# PCB-CMB-6.net
KiCad netlist of a schematic drawn in EAGLE
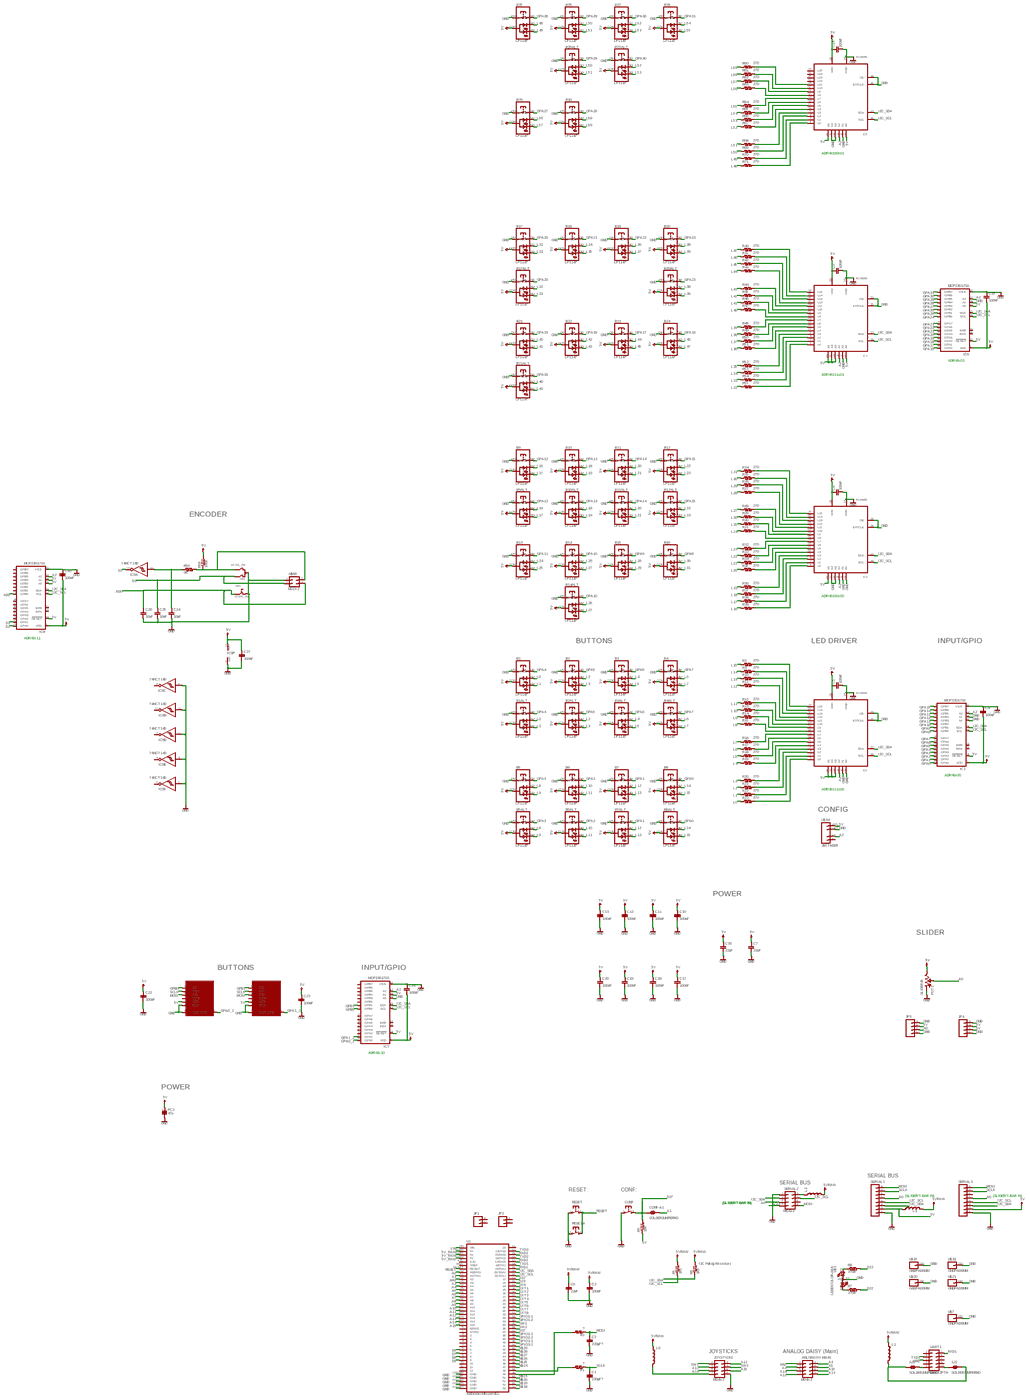
[diagram p0: schematic, sheet 1, overview]
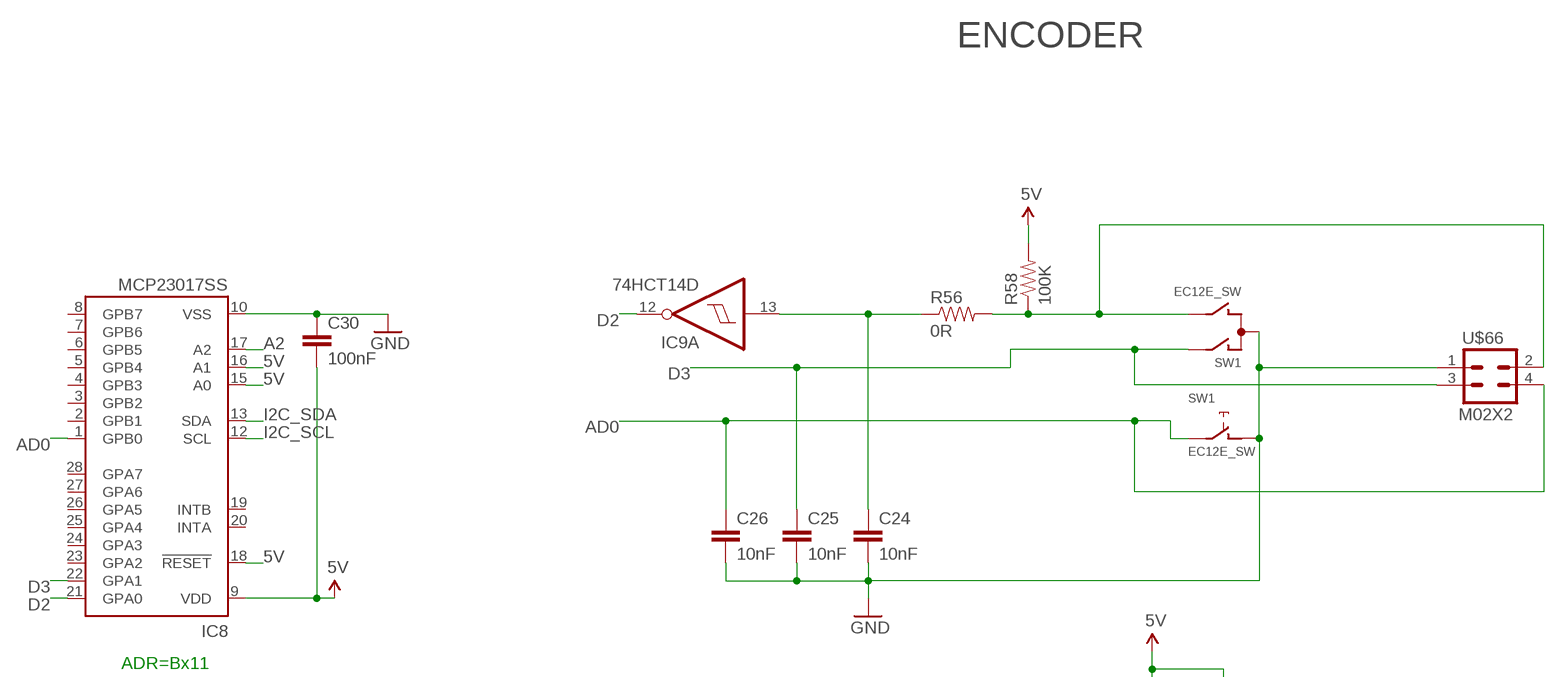
[diagram p1: schematic, sheet 1, part 1 of 6]
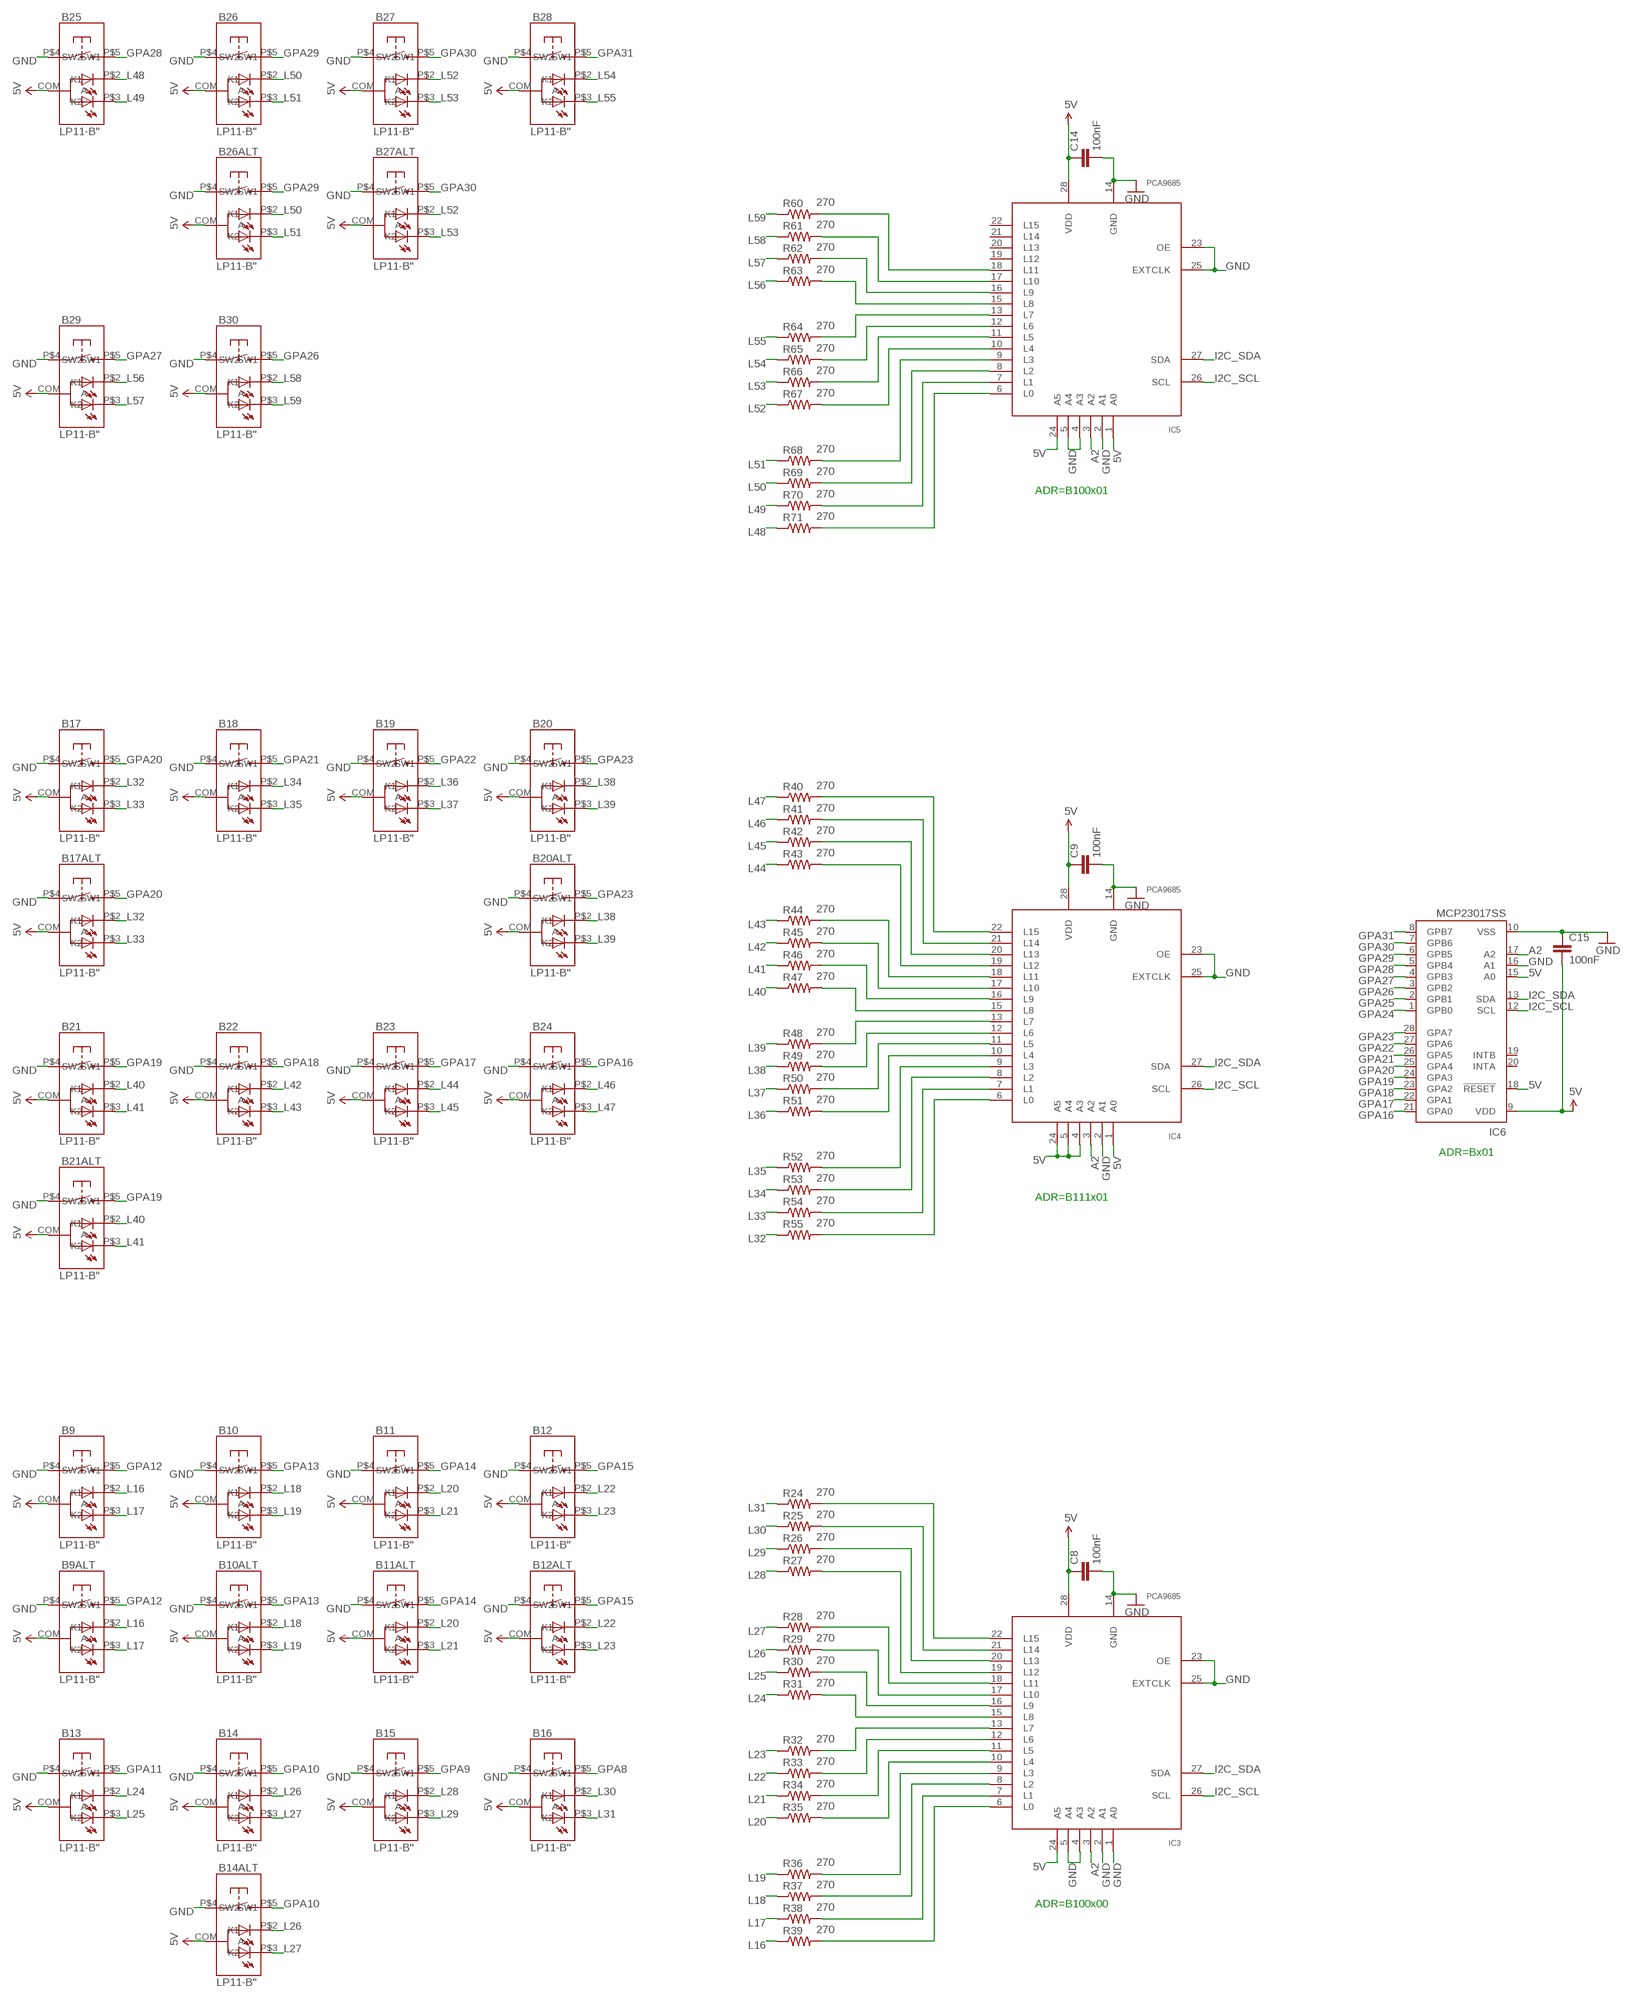
[diagram p2: schematic, sheet 1, part 2 of 6]
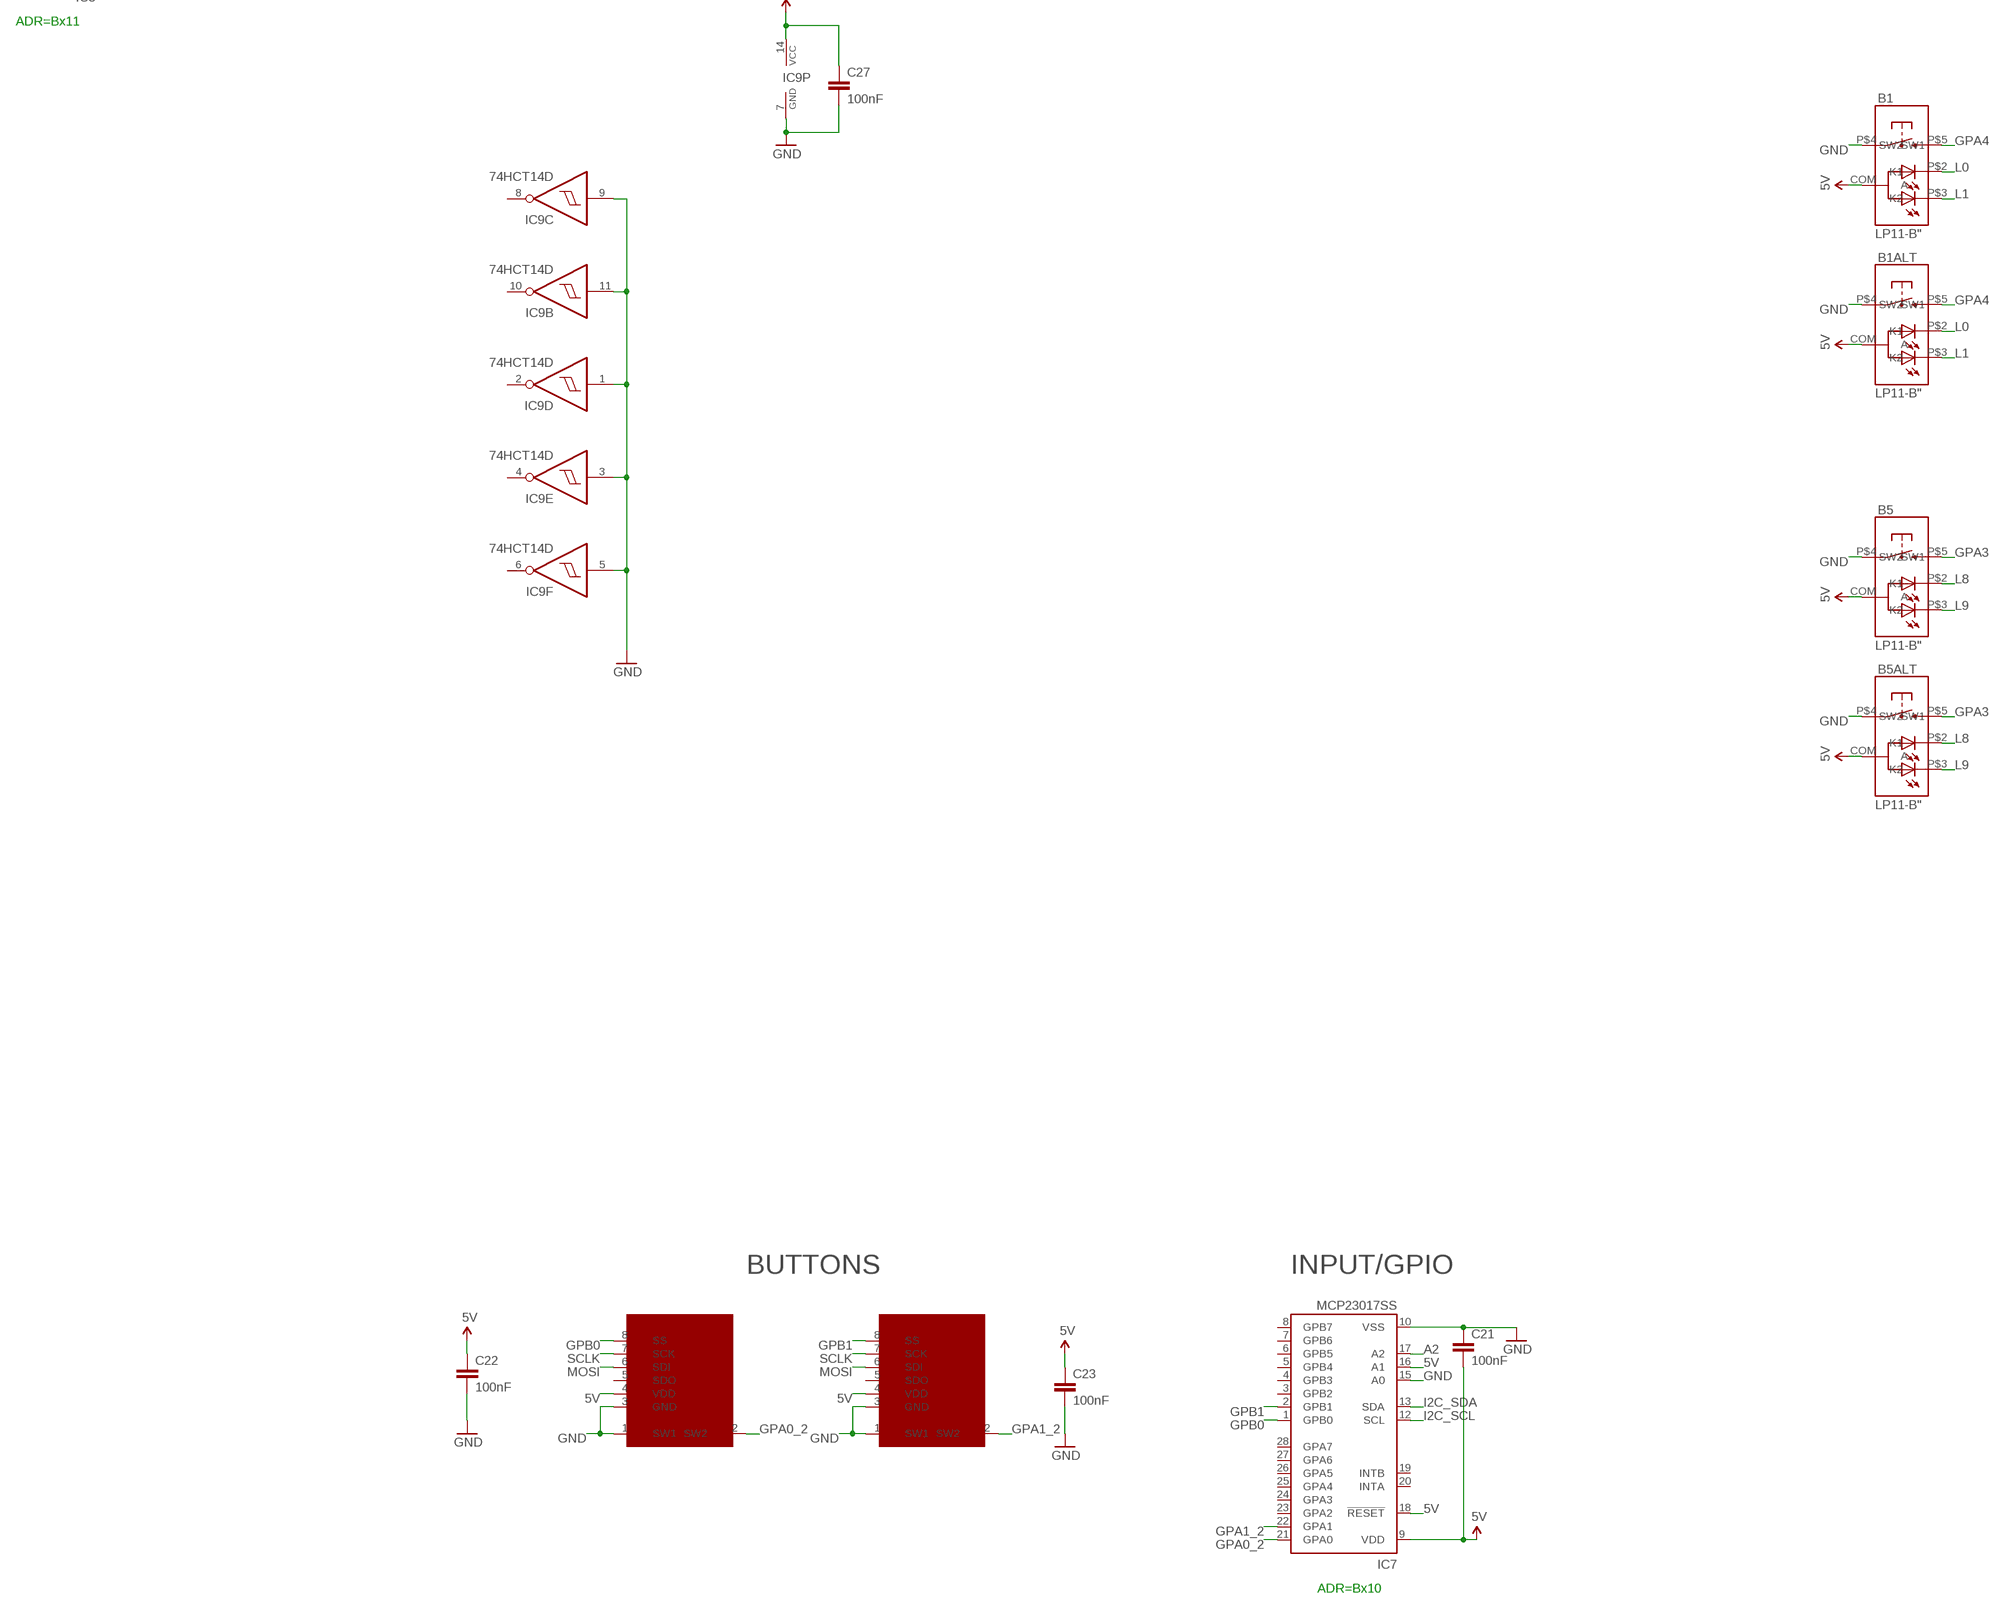
[diagram p3: schematic, sheet 1, part 3 of 6]
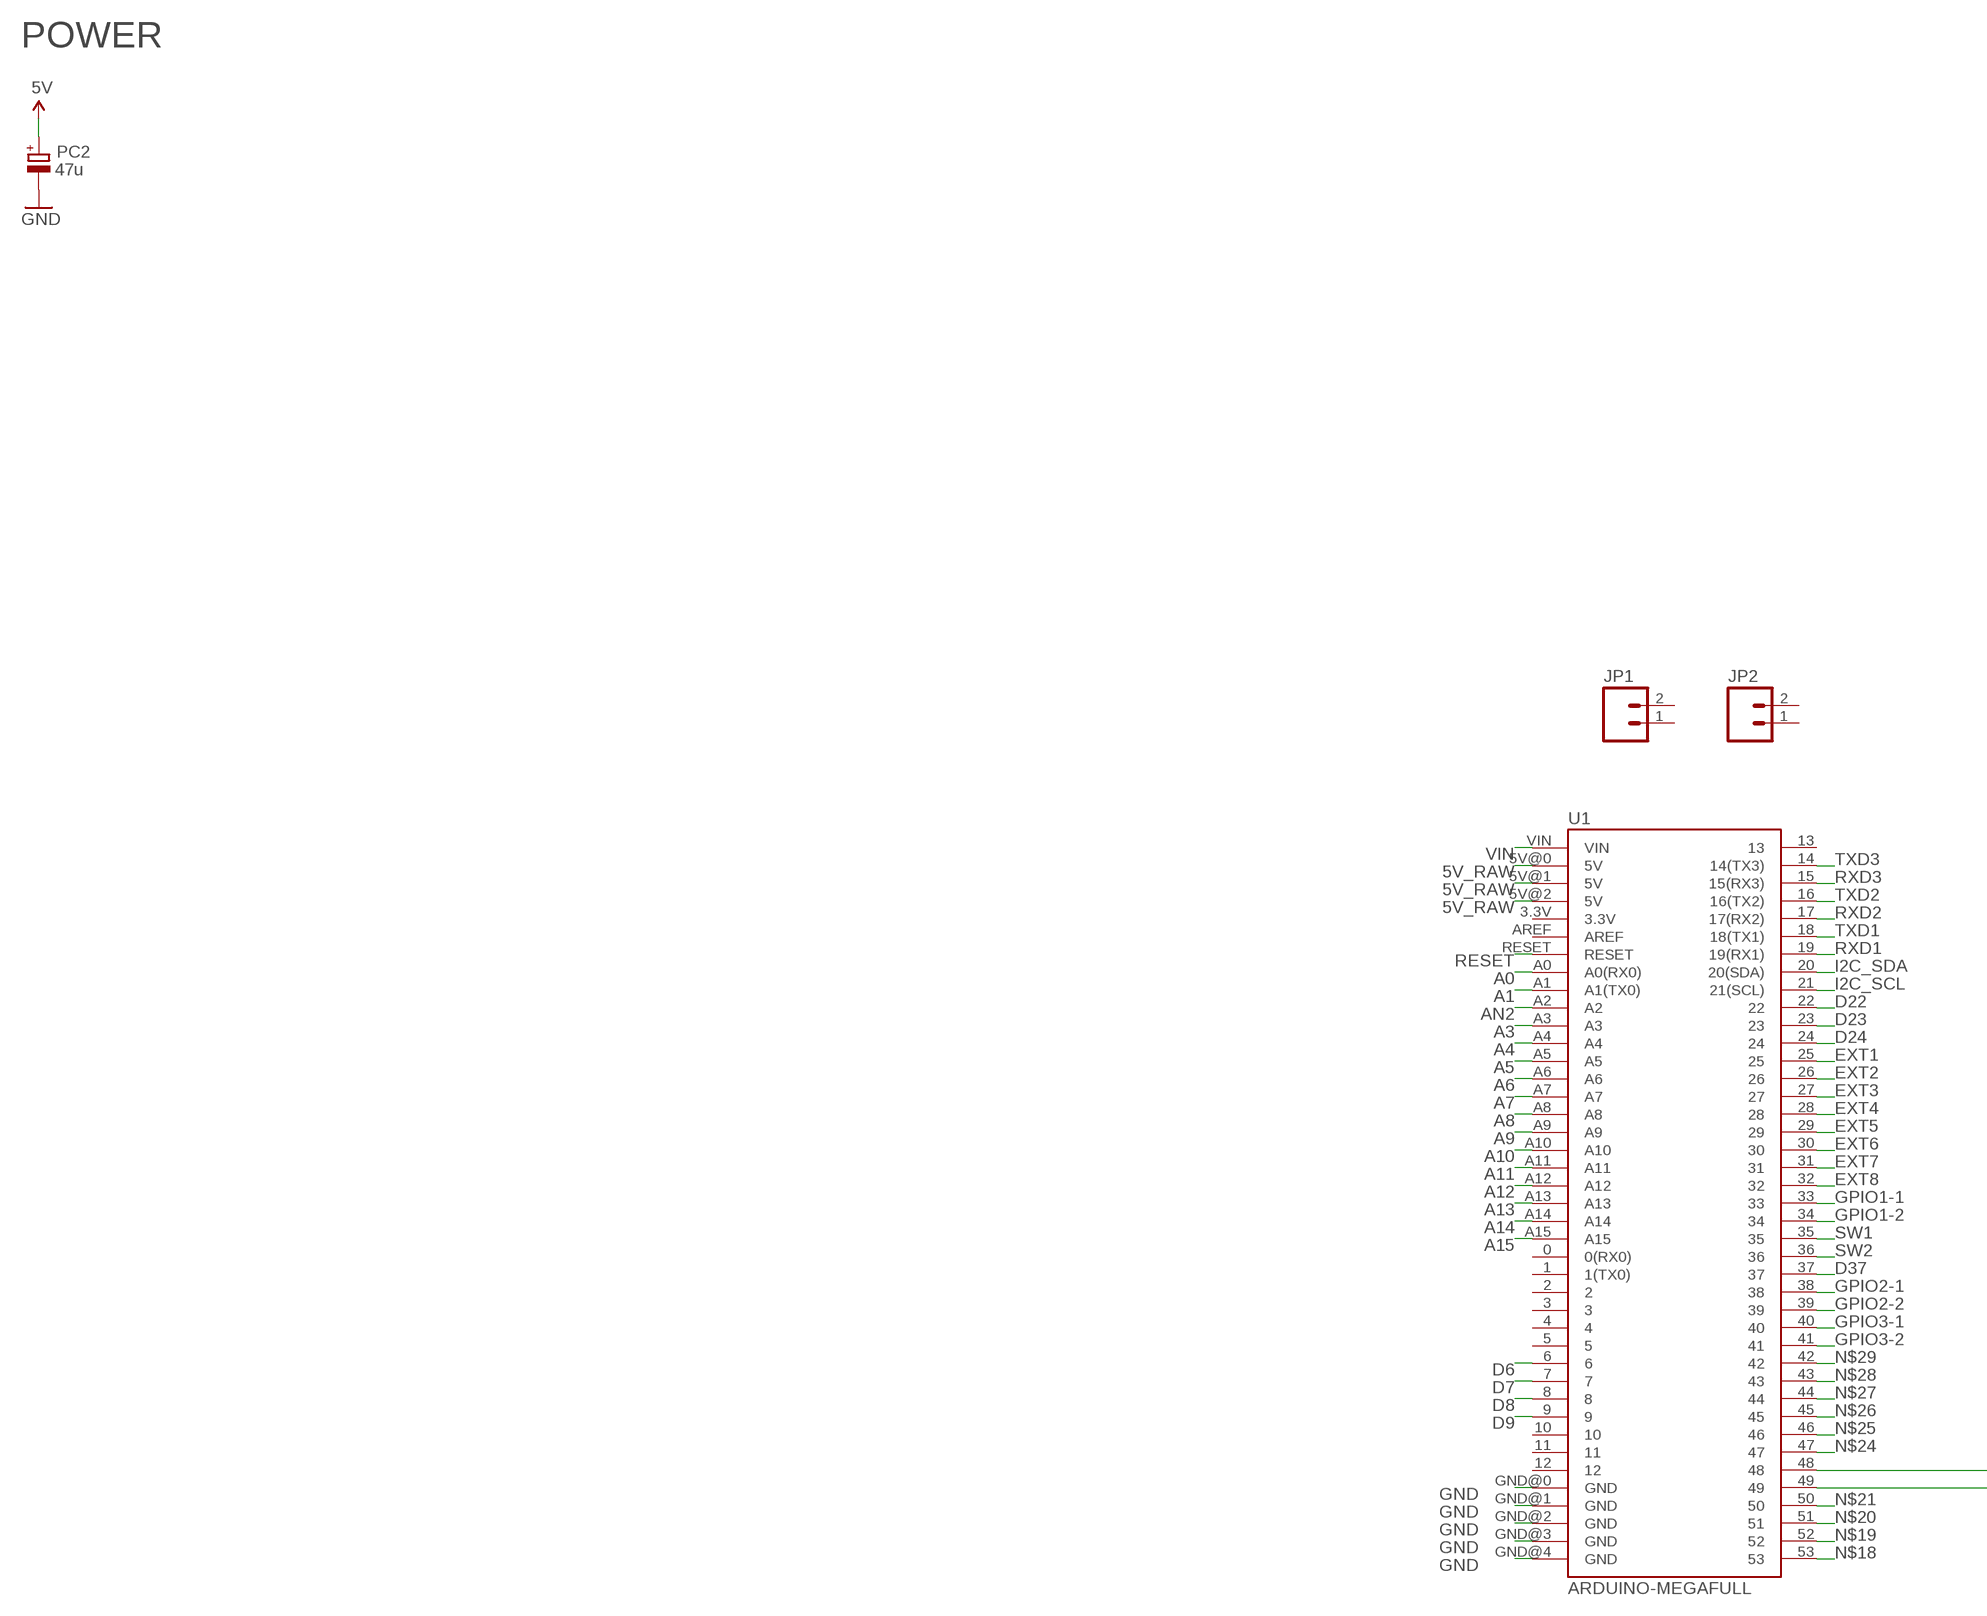
[diagram p4: schematic, sheet 1, part 4 of 6]
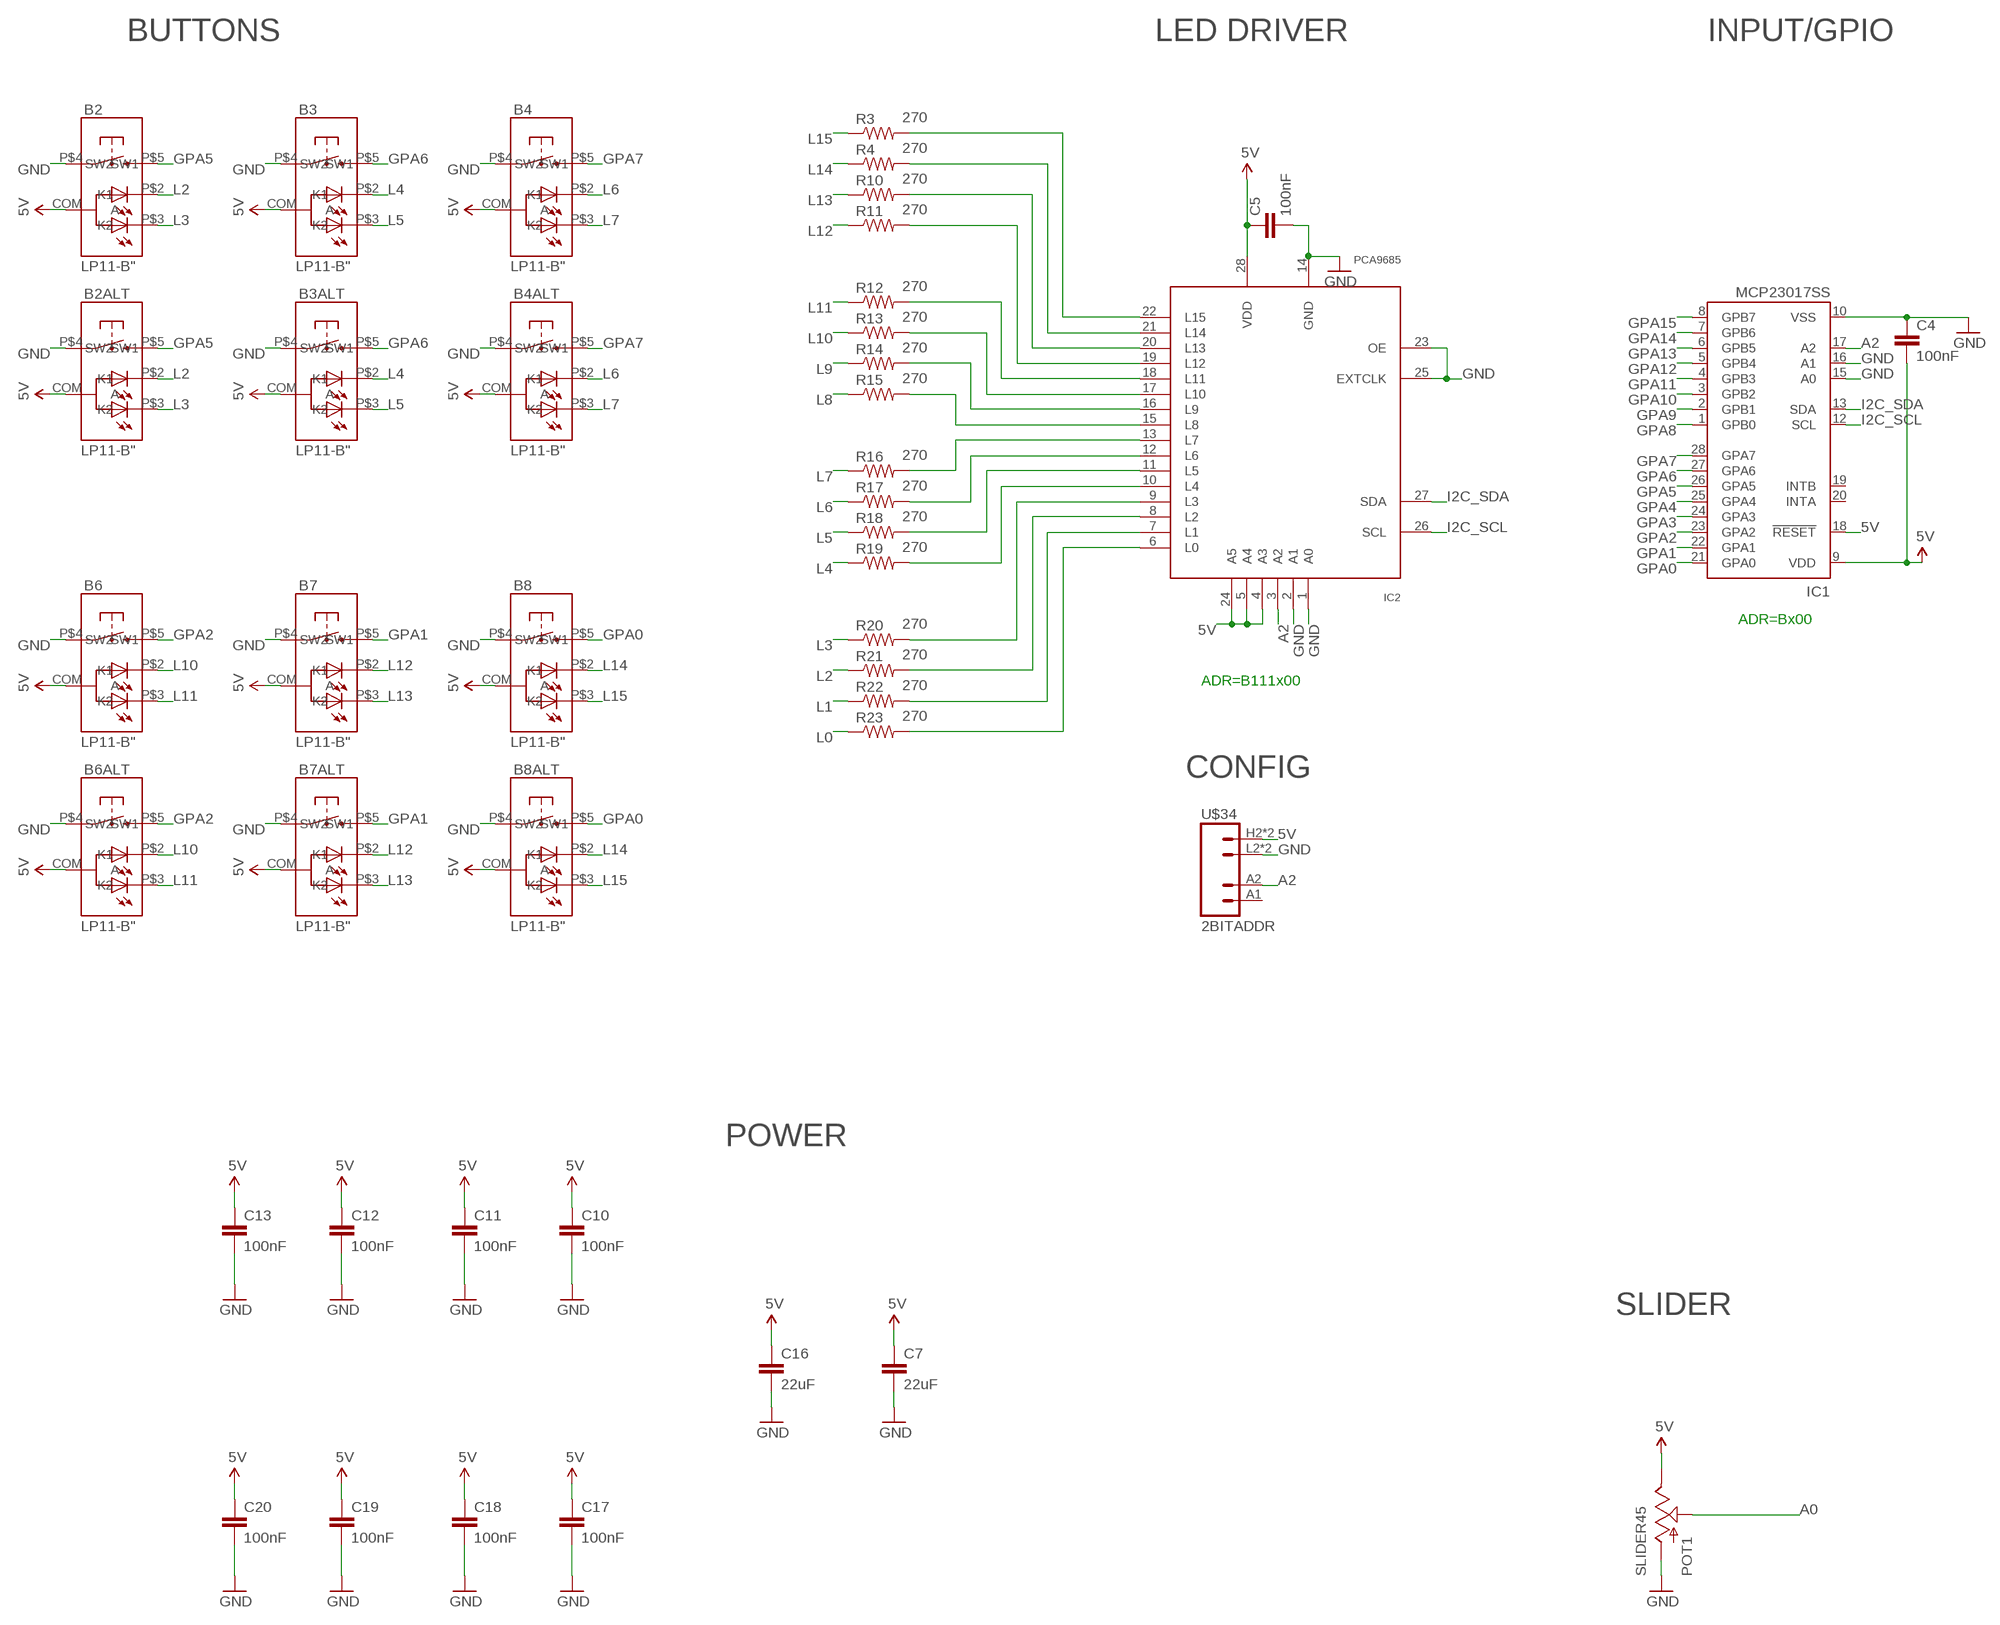
[diagram p5: schematic, sheet 1, part 5 of 6]
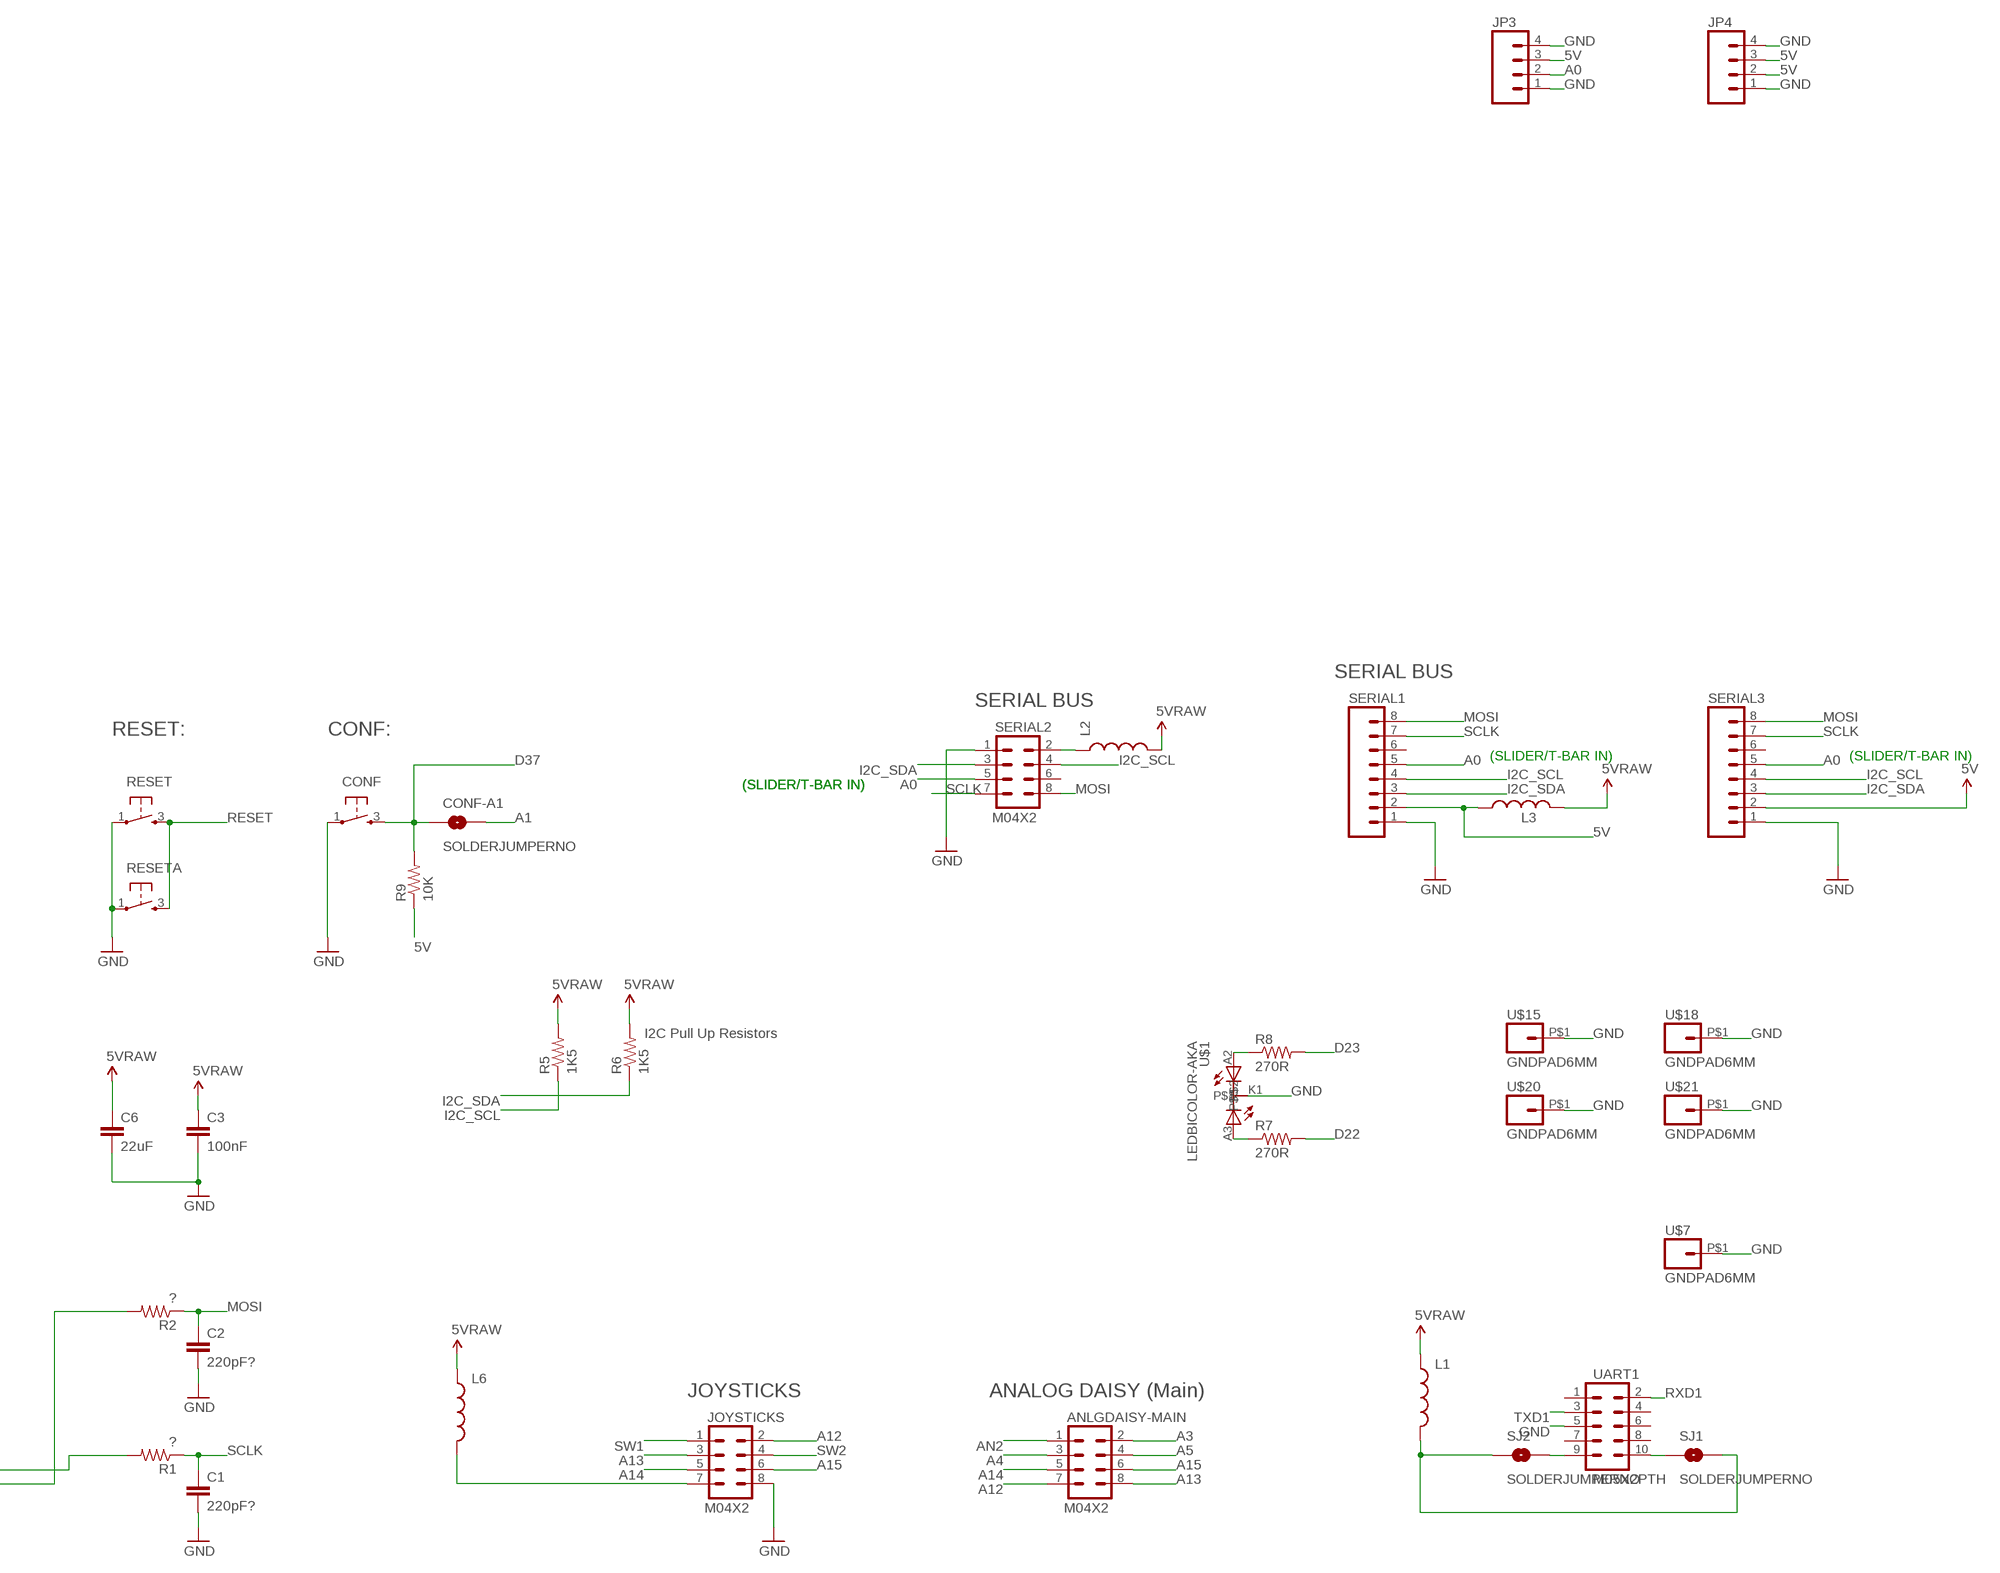
[diagram p6: schematic, sheet 1, part 6 of 6]

(export (version "E")
  (design (tool "Eeschema 10.0.6"))
  (components
    (comp (ref "ANLGDAISY-MAIN")
      (value "M04X2")
      (footprint "eagle-import:2X4")
      (libsource (lib "eagle-import") (part "M04X2"))
    )
    (comp (ref "B1")
      (value "LP11-B\"")
      (footprint "eagle-import:LP11")
      (libsource (lib "eagle-import") (part "LP11-B{dblquote}"))
    )
    (comp (ref "B1ALT")
      (value "LP11-B\"")
      (footprint "eagle-import:LP11")
      (libsource (lib "eagle-import") (part "LP11-B{dblquote}"))
    )
    (comp (ref "B2")
      (value "LP11-B\"")
      (footprint "eagle-import:LP11")
      (libsource (lib "eagle-import") (part "LP11-B{dblquote}"))
    )
    (comp (ref "B2ALT")
      (value "LP11-B\"")
      (footprint "eagle-import:LP11")
      (libsource (lib "eagle-import") (part "LP11-B{dblquote}"))
    )
    (comp (ref "B3")
      (value "LP11-B\"")
      (footprint "eagle-import:LP11")
      (libsource (lib "eagle-import") (part "LP11-B{dblquote}"))
    )
    (comp (ref "B3ALT")
      (value "LP11-B\"")
      (footprint "eagle-import:LP11")
      (libsource (lib "eagle-import") (part "LP11-B{dblquote}"))
    )
    (comp (ref "B4")
      (value "LP11-B\"")
      (footprint "eagle-import:LP11")
      (libsource (lib "eagle-import") (part "LP11-B{dblquote}"))
    )
    (comp (ref "B4ALT")
      (value "LP11-B\"")
      (footprint "eagle-import:LP11")
      (libsource (lib "eagle-import") (part "LP11-B{dblquote}"))
    )
    (comp (ref "B5")
      (value "LP11-B\"")
      (footprint "eagle-import:LP11")
      (libsource (lib "eagle-import") (part "LP11-B{dblquote}"))
    )
    (comp (ref "B5ALT")
      (value "LP11-B\"")
      (footprint "eagle-import:LP11")
      (libsource (lib "eagle-import") (part "LP11-B{dblquote}"))
    )
    (comp (ref "B6")
      (value "LP11-B\"")
      (footprint "eagle-import:LP11")
      (libsource (lib "eagle-import") (part "LP11-B{dblquote}"))
    )
    (comp (ref "B6ALT")
      (value "LP11-B\"")
      (footprint "eagle-import:LP11")
      (libsource (lib "eagle-import") (part "LP11-B{dblquote}"))
    )
    (comp (ref "B7")
      (value "LP11-B\"")
      (footprint "eagle-import:LP11")
      (libsource (lib "eagle-import") (part "LP11-B{dblquote}"))
    )
    (comp (ref "B7ALT")
      (value "LP11-B\"")
      (footprint "eagle-import:LP11")
      (libsource (lib "eagle-import") (part "LP11-B{dblquote}"))
    )
    (comp (ref "B8")
      (value "LP11-B\"")
      (footprint "eagle-import:LP11")
      (libsource (lib "eagle-import") (part "LP11-B{dblquote}"))
    )
    (comp (ref "B8ALT")
      (value "LP11-B\"")
      (footprint "eagle-import:LP11")
      (libsource (lib "eagle-import") (part "LP11-B{dblquote}"))
    )
    (comp (ref "B9")
      (value "LP11-B\"")
      (footprint "eagle-import:LP11")
      (libsource (lib "eagle-import") (part "LP11-B{dblquote}"))
    )
    (comp (ref "B9ALT")
      (value "LP11-B\"")
      (footprint "eagle-import:LP11")
      (libsource (lib "eagle-import") (part "LP11-B{dblquote}"))
    )
    (comp (ref "B10")
      (value "LP11-B\"")
      (footprint "eagle-import:LP11")
      (libsource (lib "eagle-import") (part "LP11-B{dblquote}"))
    )
    (comp (ref "B10ALT")
      (value "LP11-B\"")
      (footprint "eagle-import:LP11")
      (libsource (lib "eagle-import") (part "LP11-B{dblquote}"))
    )
    (comp (ref "B11")
      (value "LP11-B\"")
      (footprint "eagle-import:LP11")
      (libsource (lib "eagle-import") (part "LP11-B{dblquote}"))
    )
    (comp (ref "B11ALT")
      (value "LP11-B\"")
      (footprint "eagle-import:LP11")
      (libsource (lib "eagle-import") (part "LP11-B{dblquote}"))
    )
    (comp (ref "B12")
      (value "LP11-B\"")
      (footprint "eagle-import:LP11")
      (libsource (lib "eagle-import") (part "LP11-B{dblquote}"))
    )
    (comp (ref "B12ALT")
      (value "LP11-B\"")
      (footprint "eagle-import:LP11")
      (libsource (lib "eagle-import") (part "LP11-B{dblquote}"))
    )
    (comp (ref "B13")
      (value "LP11-B\"")
      (footprint "eagle-import:LP11")
      (libsource (lib "eagle-import") (part "LP11-B{dblquote}"))
    )
    (comp (ref "B14")
      (value "LP11-B\"")
      (footprint "eagle-import:LP11")
      (libsource (lib "eagle-import") (part "LP11-B{dblquote}"))
    )
    (comp (ref "B14ALT")
      (value "LP11-B\"")
      (footprint "eagle-import:LP11")
      (libsource (lib "eagle-import") (part "LP11-B{dblquote}"))
    )
    (comp (ref "B15")
      (value "LP11-B\"")
      (footprint "eagle-import:LP11")
      (libsource (lib "eagle-import") (part "LP11-B{dblquote}"))
    )
    (comp (ref "B16")
      (value "LP11-B\"")
      (footprint "eagle-import:LP11")
      (libsource (lib "eagle-import") (part "LP11-B{dblquote}"))
    )
    (comp (ref "B17")
      (value "LP11-B\"")
      (footprint "eagle-import:LP11")
      (libsource (lib "eagle-import") (part "LP11-B{dblquote}"))
    )
    (comp (ref "B17ALT")
      (value "LP11-B\"")
      (footprint "eagle-import:LP11")
      (libsource (lib "eagle-import") (part "LP11-B{dblquote}"))
    )
    (comp (ref "B18")
      (value "LP11-B\"")
      (footprint "eagle-import:LP11")
      (libsource (lib "eagle-import") (part "LP11-B{dblquote}"))
    )
    (comp (ref "B19")
      (value "LP11-B\"")
      (footprint "eagle-import:LP11")
      (libsource (lib "eagle-import") (part "LP11-B{dblquote}"))
    )
    (comp (ref "B20")
      (value "LP11-B\"")
      (footprint "eagle-import:LP11")
      (libsource (lib "eagle-import") (part "LP11-B{dblquote}"))
    )
    (comp (ref "B20ALT")
      (value "LP11-B\"")
      (footprint "eagle-import:LP11")
      (libsource (lib "eagle-import") (part "LP11-B{dblquote}"))
    )
    (comp (ref "B21")
      (value "LP11-B\"")
      (footprint "eagle-import:LP11")
      (libsource (lib "eagle-import") (part "LP11-B{dblquote}"))
    )
    (comp (ref "B21ALT")
      (value "LP11-B\"")
      (footprint "eagle-import:LP11")
      (libsource (lib "eagle-import") (part "LP11-B{dblquote}"))
    )
    (comp (ref "B22")
      (value "LP11-B\"")
      (footprint "eagle-import:LP11")
      (libsource (lib "eagle-import") (part "LP11-B{dblquote}"))
    )
    (comp (ref "B23")
      (value "LP11-B\"")
      (footprint "eagle-import:LP11")
      (libsource (lib "eagle-import") (part "LP11-B{dblquote}"))
    )
    (comp (ref "B24")
      (value "LP11-B\"")
      (footprint "eagle-import:LP11")
      (libsource (lib "eagle-import") (part "LP11-B{dblquote}"))
    )
    (comp (ref "B25")
      (value "LP11-B\"")
      (footprint "eagle-import:LP11")
      (libsource (lib "eagle-import") (part "LP11-B{dblquote}"))
    )
    (comp (ref "B26")
      (value "LP11-B\"")
      (footprint "eagle-import:LP11")
      (libsource (lib "eagle-import") (part "LP11-B{dblquote}"))
    )
    (comp (ref "B26ALT")
      (value "LP11-B\"")
      (footprint "eagle-import:LP11")
      (libsource (lib "eagle-import") (part "LP11-B{dblquote}"))
    )
    (comp (ref "B27")
      (value "LP11-B\"")
      (footprint "eagle-import:LP11")
      (libsource (lib "eagle-import") (part "LP11-B{dblquote}"))
    )
    (comp (ref "B27ALT")
      (value "LP11-B\"")
      (footprint "eagle-import:LP11")
      (libsource (lib "eagle-import") (part "LP11-B{dblquote}"))
    )
    (comp (ref "B28")
      (value "LP11-B\"")
      (footprint "eagle-import:LP11")
      (libsource (lib "eagle-import") (part "LP11-B{dblquote}"))
    )
    (comp (ref "B29")
      (value "LP11-B\"")
      (footprint "eagle-import:LP11")
      (libsource (lib "eagle-import") (part "LP11-B{dblquote}"))
    )
    (comp (ref "B30")
      (value "LP11-B\"")
      (footprint "eagle-import:LP11")
      (libsource (lib "eagle-import") (part "LP11-B{dblquote}"))
    )
    (comp (ref "C1")
      (value "220pF?")
      (footprint "eagle-import:0603-CAP")
      (libsource (lib "eagle-import") (part "CAP0603-CAP"))
    )
    (comp (ref "C2")
      (value "220pF?")
      (footprint "eagle-import:0603-CAP")
      (libsource (lib "eagle-import") (part "CAP0603-CAP"))
    )
    (comp (ref "C3")
      (value "100nF")
      (footprint "eagle-import:0603-CAP")
      (libsource (lib "eagle-import") (part "CAP0603-CAP"))
    )
    (comp (ref "C4")
      (value "100nF")
      (footprint "eagle-import:0603-CAP")
      (libsource (lib "eagle-import") (part "CAP0603-CAP"))
    )
    (comp (ref "C5")
      (value "100nF")
      (footprint "eagle-import:0603-CAP")
      (libsource (lib "eagle-import") (part "CAP0603-CAP"))
    )
    (comp (ref "C6")
      (value "22uF")
      (footprint "eagle-import:0805")
      (libsource (lib "eagle-import") (part "CAP0805"))
    )
    (comp (ref "C7")
      (value "22uF")
      (footprint "eagle-import:0805")
      (libsource (lib "eagle-import") (part "CAP0805"))
    )
    (comp (ref "C8")
      (value "100nF")
      (footprint "eagle-import:0603-CAP")
      (libsource (lib "eagle-import") (part "CAP0603-CAP"))
    )
    (comp (ref "C9")
      (value "100nF")
      (footprint "eagle-import:0603-CAP")
      (libsource (lib "eagle-import") (part "CAP0603-CAP"))
    )
    (comp (ref "C10")
      (value "100nF")
      (footprint "eagle-import:0603-CAP")
      (libsource (lib "eagle-import") (part "CAP0603-CAP"))
    )
    (comp (ref "C11")
      (value "100nF")
      (footprint "eagle-import:0603-CAP")
      (libsource (lib "eagle-import") (part "CAP0603-CAP"))
    )
    (comp (ref "C12")
      (value "100nF")
      (footprint "eagle-import:0603-CAP")
      (libsource (lib "eagle-import") (part "CAP0603-CAP"))
    )
    (comp (ref "C13")
      (value "100nF")
      (footprint "eagle-import:0603-CAP")
      (libsource (lib "eagle-import") (part "CAP0603-CAP"))
    )
    (comp (ref "C14")
      (value "100nF")
      (footprint "eagle-import:0603-CAP")
      (libsource (lib "eagle-import") (part "CAP0603-CAP"))
    )
    (comp (ref "C15")
      (value "100nF")
      (footprint "eagle-import:0603-CAP")
      (libsource (lib "eagle-import") (part "CAP0603-CAP"))
    )
    (comp (ref "C16")
      (value "22uF")
      (footprint "eagle-import:0805")
      (libsource (lib "eagle-import") (part "CAP0805"))
    )
    (comp (ref "C17")
      (value "100nF")
      (footprint "eagle-import:0603-CAP")
      (libsource (lib "eagle-import") (part "CAP0603-CAP"))
    )
    (comp (ref "C18")
      (value "100nF")
      (footprint "eagle-import:0603-CAP")
      (libsource (lib "eagle-import") (part "CAP0603-CAP"))
    )
    (comp (ref "C19")
      (value "100nF")
      (footprint "eagle-import:0603-CAP")
      (libsource (lib "eagle-import") (part "CAP0603-CAP"))
    )
    (comp (ref "C20")
      (value "100nF")
      (footprint "eagle-import:0603-CAP")
      (libsource (lib "eagle-import") (part "CAP0603-CAP"))
    )
    (comp (ref "C21")
      (value "100nF")
      (footprint "eagle-import:0603-CAP")
      (libsource (lib "eagle-import") (part "CAP0603-CAP"))
    )
    (comp (ref "C22")
      (value "100nF")
      (footprint "eagle-import:0603-CAP")
      (libsource (lib "eagle-import") (part "CAP0603-CAP"))
    )
    (comp (ref "C23")
      (value "100nF")
      (footprint "eagle-import:0603-CAP")
      (libsource (lib "eagle-import") (part "CAP0603-CAP"))
    )
    (comp (ref "C24")
      (value "10nF")
      (footprint "eagle-import:0603-CAP")
      (libsource (lib "eagle-import") (part "CAP0603-CAP"))
    )
    (comp (ref "C25")
      (value "10nF")
      (footprint "eagle-import:0603-CAP")
      (libsource (lib "eagle-import") (part "CAP0603-CAP"))
    )
    (comp (ref "C26")
      (value "10nF")
      (footprint "eagle-import:0603-CAP")
      (libsource (lib "eagle-import") (part "CAP0603-CAP"))
    )
    (comp (ref "C27")
      (value "100nF")
      (footprint "eagle-import:0603-CAP")
      (libsource (lib "eagle-import") (part "CAP0603-CAP"))
    )
    (comp (ref "C30")
      (value "100nF")
      (footprint "eagle-import:0603-CAP")
      (libsource (lib "eagle-import") (part "CAP0603-CAP"))
    )
    (comp (ref "CONF")
      (value "TAC_SWITCH")
      (footprint "eagle-import:PUSHBUTTON")
      (libsource (lib "eagle-import") (part "TAC_SWITCH"))
    )
    (comp (ref "CONF-A1")
      (value "SOLDERJUMPERNO")
      (footprint "eagle-import:SJ_2S-NO")
      (libsource (lib "eagle-import") (part "SOLDERJUMPERNO"))
    )
    (comp (ref "IC1")
      (value "MCP23017SS")
      (footprint "eagle-import:SSOP28")
      (fields
        (field (name "MF") "MICROCHIP")
        (field (name "MPN") "MCP23017-E/SS")
        (field (name "MPN_1") "MCP23017-E/SS")
        (field (name "OC_FARNELL") "1467674")
        (field (name "OC_NEWARK") "31K2960")
      )
      (libsource (lib "eagle-import") (part "MCP23017SS"))
    )
    (comp (ref "IC2")
      (value "PCA9685")
      (footprint "eagle-import:TSSOP28")
      (libsource (lib "eagle-import") (part "PCA9685"))
    )
    (comp (ref "IC3")
      (value "PCA9685")
      (footprint "eagle-import:TSSOP28")
      (libsource (lib "eagle-import") (part "PCA9685"))
    )
    (comp (ref "IC4")
      (value "PCA9685")
      (footprint "eagle-import:TSSOP28")
      (libsource (lib "eagle-import") (part "PCA9685"))
    )
    (comp (ref "IC5")
      (value "PCA9685")
      (footprint "eagle-import:TSSOP28")
      (libsource (lib "eagle-import") (part "PCA9685"))
    )
    (comp (ref "IC6")
      (value "MCP23017SS")
      (footprint "eagle-import:SSOP28")
      (fields
        (field (name "MF") "MICROCHIP")
        (field (name "MPN") "MCP23017-E/SS")
        (field (name "MPN_1") "MCP23017-E/SS")
        (field (name "OC_FARNELL") "1467674")
        (field (name "OC_NEWARK") "31K2960")
      )
      (libsource (lib "eagle-import") (part "MCP23017SS"))
    )
    (comp (ref "IC7")
      (value "MCP23017SS")
      (footprint "eagle-import:SSOP28")
      (fields
        (field (name "MF") "MICROCHIP")
        (field (name "MPN") "MCP23017-E/SS")
        (field (name "MPN_1") "MCP23017-E/SS")
        (field (name "OC_FARNELL") "1467674")
        (field (name "OC_NEWARK") "31K2960")
      )
      (libsource (lib "eagle-import") (part "MCP23017SS"))
    )
    (comp (ref "IC8")
      (value "MCP23017SS")
      (footprint "eagle-import:SSOP28")
      (fields
        (field (name "MF") "MICROCHIP")
        (field (name "MPN") "MCP23017-E/SS")
        (field (name "MPN_1") "MCP23017-E/SS")
        (field (name "OC_FARNELL") "1467674")
        (field (name "OC_NEWARK") "31K2960")
      )
      (libsource (lib "eagle-import") (part "MCP23017SS"))
    )
    (comp (ref "IC9")
      (value "74HCT14D")
      (footprint "eagle-import:SO14")
      (libsource (lib "eagle-import") (part "7414DHCT"))
    )
    (comp (ref "JOYSTICKS")
      (value "M04X2")
      (footprint "eagle-import:2X4")
      (libsource (lib "eagle-import") (part "M04X2"))
    )
    (comp (ref "JP1")
      (value "M02PTH")
      (footprint "eagle-import:1X02")
      (libsource (lib "eagle-import") (part "M02PTH"))
    )
    (comp (ref "JP2")
      (value "M02PTH")
      (footprint "eagle-import:1X02")
      (libsource (lib "eagle-import") (part "M02PTH"))
    )
    (comp (ref "JP3")
      (value "M04PTH")
      (footprint "eagle-import:1X04")
      (libsource (lib "eagle-import") (part "M04PTH"))
    )
    (comp (ref "JP4")
      (value "M04PTH")
      (footprint "eagle-import:1X04")
      (libsource (lib "eagle-import") (part "M04PTH"))
    )
    (comp (ref "L1")
      (value "INDUCTOR0805")
      (footprint "eagle-import:0805")
      (libsource (lib "eagle-import") (part "INDUCTOR0805"))
    )
    (comp (ref "L2")
      (value "INDUCTOR0805")
      (footprint "eagle-import:0805")
      (libsource (lib "eagle-import") (part "INDUCTOR0805"))
    )
    (comp (ref "L3")
      (value "INDUCTOR0805")
      (footprint "eagle-import:0805")
      (libsource (lib "eagle-import") (part "INDUCTOR0805"))
    )
    (comp (ref "L6")
      (value "INDUCTOR0805")
      (footprint "eagle-import:0805")
      (libsource (lib "eagle-import") (part "INDUCTOR0805"))
    )
    (comp (ref "PC2")
      (value "47u")
      (footprint "eagle-import:PANASONIC_D")
      (libsource (lib "eagle-import") (part "CPOL-EUD"))
    )
    (comp (ref "POT1")
      (value "SLIDER45")
      (footprint "eagle-import:SLIDER45")
      (libsource (lib "eagle-import") (part "SLIDER45"))
    )
    (comp (ref "R1")
      (value "?")
      (footprint "eagle-import:0603-RES")
      (libsource (lib "eagle-import") (part "RESISTOR0603-RES"))
    )
    (comp (ref "R2")
      (value "?")
      (footprint "eagle-import:0603-RES")
      (libsource (lib "eagle-import") (part "RESISTOR0603-RES"))
    )
    (comp (ref "R3")
      (value "270")
      (footprint "eagle-import:0603-RES")
      (libsource (lib "eagle-import") (part "RESISTOR0603-RES"))
    )
    (comp (ref "R4")
      (value "270")
      (footprint "eagle-import:0603-RES")
      (libsource (lib "eagle-import") (part "RESISTOR0603-RES"))
    )
    (comp (ref "R5")
      (value "1K5")
      (footprint "eagle-import:0603-RES")
      (libsource (lib "eagle-import") (part "RESISTOR0603-RES"))
    )
    (comp (ref "R6")
      (value "1K5")
      (footprint "eagle-import:0603-RES")
      (libsource (lib "eagle-import") (part "RESISTOR0603-RES"))
    )
    (comp (ref "R7")
      (value "270R")
      (footprint "eagle-import:0603-RES")
      (libsource (lib "eagle-import") (part "RESISTOR0603-RES"))
    )
    (comp (ref "R8")
      (value "270R")
      (footprint "eagle-import:0603-RES")
      (libsource (lib "eagle-import") (part "RESISTOR0603-RES"))
    )
    (comp (ref "R9")
      (value "10K")
      (footprint "eagle-import:0603-RES")
      (libsource (lib "eagle-import") (part "RESISTOR0603-RES"))
    )
    (comp (ref "R10")
      (value "270")
      (footprint "eagle-import:0603-RES")
      (libsource (lib "eagle-import") (part "RESISTOR0603-RES"))
    )
    (comp (ref "R11")
      (value "270")
      (footprint "eagle-import:0603-RES")
      (libsource (lib "eagle-import") (part "RESISTOR0603-RES"))
    )
    (comp (ref "R12")
      (value "270")
      (footprint "eagle-import:0603-RES")
      (libsource (lib "eagle-import") (part "RESISTOR0603-RES"))
    )
    (comp (ref "R13")
      (value "270")
      (footprint "eagle-import:0603-RES")
      (libsource (lib "eagle-import") (part "RESISTOR0603-RES"))
    )
    (comp (ref "R14")
      (value "270")
      (footprint "eagle-import:0603-RES")
      (libsource (lib "eagle-import") (part "RESISTOR0603-RES"))
    )
    (comp (ref "R15")
      (value "270")
      (footprint "eagle-import:0603-RES")
      (libsource (lib "eagle-import") (part "RESISTOR0603-RES"))
    )
    (comp (ref "R16")
      (value "270")
      (footprint "eagle-import:0603-RES")
      (libsource (lib "eagle-import") (part "RESISTOR0603-RES"))
    )
    (comp (ref "R17")
      (value "270")
      (footprint "eagle-import:0603-RES")
      (libsource (lib "eagle-import") (part "RESISTOR0603-RES"))
    )
    (comp (ref "R18")
      (value "270")
      (footprint "eagle-import:0603-RES")
      (libsource (lib "eagle-import") (part "RESISTOR0603-RES"))
    )
    (comp (ref "R19")
      (value "270")
      (footprint "eagle-import:0603-RES")
      (libsource (lib "eagle-import") (part "RESISTOR0603-RES"))
    )
    (comp (ref "R20")
      (value "270")
      (footprint "eagle-import:0603-RES")
      (libsource (lib "eagle-import") (part "RESISTOR0603-RES"))
    )
    (comp (ref "R21")
      (value "270")
      (footprint "eagle-import:0603-RES")
      (libsource (lib "eagle-import") (part "RESISTOR0603-RES"))
    )
    (comp (ref "R22")
      (value "270")
      (footprint "eagle-import:0603-RES")
      (libsource (lib "eagle-import") (part "RESISTOR0603-RES"))
    )
    (comp (ref "R23")
      (value "270")
      (footprint "eagle-import:0603-RES")
      (libsource (lib "eagle-import") (part "RESISTOR0603-RES"))
    )
    (comp (ref "R24")
      (value "270")
      (footprint "eagle-import:0603-RES")
      (libsource (lib "eagle-import") (part "RESISTOR0603-RES"))
    )
    (comp (ref "R25")
      (value "270")
      (footprint "eagle-import:0603-RES")
      (libsource (lib "eagle-import") (part "RESISTOR0603-RES"))
    )
    (comp (ref "R26")
      (value "270")
      (footprint "eagle-import:0603-RES")
      (libsource (lib "eagle-import") (part "RESISTOR0603-RES"))
    )
    (comp (ref "R27")
      (value "270")
      (footprint "eagle-import:0603-RES")
      (libsource (lib "eagle-import") (part "RESISTOR0603-RES"))
    )
    (comp (ref "R28")
      (value "270")
      (footprint "eagle-import:0603-RES")
      (libsource (lib "eagle-import") (part "RESISTOR0603-RES"))
    )
    (comp (ref "R29")
      (value "270")
      (footprint "eagle-import:0603-RES")
      (libsource (lib "eagle-import") (part "RESISTOR0603-RES"))
    )
    (comp (ref "R30")
      (value "270")
      (footprint "eagle-import:0603-RES")
      (libsource (lib "eagle-import") (part "RESISTOR0603-RES"))
    )
    (comp (ref "R31")
      (value "270")
      (footprint "eagle-import:0603-RES")
      (libsource (lib "eagle-import") (part "RESISTOR0603-RES"))
    )
    (comp (ref "R32")
      (value "270")
      (footprint "eagle-import:0603-RES")
      (libsource (lib "eagle-import") (part "RESISTOR0603-RES"))
    )
    (comp (ref "R33")
      (value "270")
      (footprint "eagle-import:0603-RES")
      (libsource (lib "eagle-import") (part "RESISTOR0603-RES"))
    )
    (comp (ref "R34")
      (value "270")
      (footprint "eagle-import:0603-RES")
      (libsource (lib "eagle-import") (part "RESISTOR0603-RES"))
    )
    (comp (ref "R35")
      (value "270")
      (footprint "eagle-import:0603-RES")
      (libsource (lib "eagle-import") (part "RESISTOR0603-RES"))
    )
    (comp (ref "R36")
      (value "270")
      (footprint "eagle-import:0603-RES")
      (libsource (lib "eagle-import") (part "RESISTOR0603-RES"))
    )
    (comp (ref "R37")
      (value "270")
      (footprint "eagle-import:0603-RES")
      (libsource (lib "eagle-import") (part "RESISTOR0603-RES"))
    )
    (comp (ref "R38")
      (value "270")
      (footprint "eagle-import:0603-RES")
      (libsource (lib "eagle-import") (part "RESISTOR0603-RES"))
    )
    (comp (ref "R39")
      (value "270")
      (footprint "eagle-import:0603-RES")
      (libsource (lib "eagle-import") (part "RESISTOR0603-RES"))
    )
    (comp (ref "R40")
      (value "270")
      (footprint "eagle-import:0603-RES")
      (libsource (lib "eagle-import") (part "RESISTOR0603-RES"))
    )
    (comp (ref "R41")
      (value "270")
      (footprint "eagle-import:0603-RES")
      (libsource (lib "eagle-import") (part "RESISTOR0603-RES"))
    )
    (comp (ref "R42")
      (value "270")
      (footprint "eagle-import:0603-RES")
      (libsource (lib "eagle-import") (part "RESISTOR0603-RES"))
    )
    (comp (ref "R43")
      (value "270")
      (footprint "eagle-import:0603-RES")
      (libsource (lib "eagle-import") (part "RESISTOR0603-RES"))
    )
    (comp (ref "R44")
      (value "270")
      (footprint "eagle-import:0603-RES")
      (libsource (lib "eagle-import") (part "RESISTOR0603-RES"))
    )
    (comp (ref "R45")
      (value "270")
      (footprint "eagle-import:0603-RES")
      (libsource (lib "eagle-import") (part "RESISTOR0603-RES"))
    )
    (comp (ref "R46")
      (value "270")
      (footprint "eagle-import:0603-RES")
      (libsource (lib "eagle-import") (part "RESISTOR0603-RES"))
    )
    (comp (ref "R47")
      (value "270")
      (footprint "eagle-import:0603-RES")
      (libsource (lib "eagle-import") (part "RESISTOR0603-RES"))
    )
    (comp (ref "R48")
      (value "270")
      (footprint "eagle-import:0603-RES")
      (libsource (lib "eagle-import") (part "RESISTOR0603-RES"))
    )
    (comp (ref "R49")
      (value "270")
      (footprint "eagle-import:0603-RES")
      (libsource (lib "eagle-import") (part "RESISTOR0603-RES"))
    )
    (comp (ref "R50")
      (value "270")
      (footprint "eagle-import:0603-RES")
      (libsource (lib "eagle-import") (part "RESISTOR0603-RES"))
    )
    (comp (ref "R51")
      (value "270")
      (footprint "eagle-import:0603-RES")
      (libsource (lib "eagle-import") (part "RESISTOR0603-RES"))
    )
    (comp (ref "R52")
      (value "270")
      (footprint "eagle-import:0603-RES")
      (libsource (lib "eagle-import") (part "RESISTOR0603-RES"))
    )
    (comp (ref "R53")
      (value "270")
      (footprint "eagle-import:0603-RES")
      (libsource (lib "eagle-import") (part "RESISTOR0603-RES"))
    )
    (comp (ref "R54")
      (value "270")
      (footprint "eagle-import:0603-RES")
      (libsource (lib "eagle-import") (part "RESISTOR0603-RES"))
    )
    (comp (ref "R55")
      (value "270")
      (footprint "eagle-import:0603-RES")
      (libsource (lib "eagle-import") (part "RESISTOR0603-RES"))
    )
    (comp (ref "R56")
      (value "0R")
      (footprint "eagle-import:0603-RES")
      (libsource (lib "eagle-import") (part "RESISTOR0603-RES"))
    )
    (comp (ref "R58")
      (value "100K")
      (footprint "eagle-import:0603-RES")
      (libsource (lib "eagle-import") (part "RESISTOR0603-RES"))
    )
    (comp (ref "R60")
      (value "270")
      (footprint "eagle-import:0603-RES")
      (libsource (lib "eagle-import") (part "RESISTOR0603-RES"))
    )
    (comp (ref "R61")
      (value "270")
      (footprint "eagle-import:0603-RES")
      (libsource (lib "eagle-import") (part "RESISTOR0603-RES"))
    )
    (comp (ref "R62")
      (value "270")
      (footprint "eagle-import:0603-RES")
      (libsource (lib "eagle-import") (part "RESISTOR0603-RES"))
    )
    (comp (ref "R63")
      (value "270")
      (footprint "eagle-import:0603-RES")
      (libsource (lib "eagle-import") (part "RESISTOR0603-RES"))
    )
    (comp (ref "R64")
      (value "270")
      (footprint "eagle-import:0603-RES")
      (libsource (lib "eagle-import") (part "RESISTOR0603-RES"))
    )
    (comp (ref "R65")
      (value "270")
      (footprint "eagle-import:0603-RES")
      (libsource (lib "eagle-import") (part "RESISTOR0603-RES"))
    )
    (comp (ref "R66")
      (value "270")
      (footprint "eagle-import:0603-RES")
      (libsource (lib "eagle-import") (part "RESISTOR0603-RES"))
    )
    (comp (ref "R67")
      (value "270")
      (footprint "eagle-import:0603-RES")
      (libsource (lib "eagle-import") (part "RESISTOR0603-RES"))
    )
    (comp (ref "R68")
      (value "270")
      (footprint "eagle-import:0603-RES")
      (libsource (lib "eagle-import") (part "RESISTOR0603-RES"))
    )
    (comp (ref "R69")
      (value "270")
      (footprint "eagle-import:0603-RES")
      (libsource (lib "eagle-import") (part "RESISTOR0603-RES"))
    )
    (comp (ref "R70")
      (value "270")
      (footprint "eagle-import:0603-RES")
      (libsource (lib "eagle-import") (part "RESISTOR0603-RES"))
    )
    (comp (ref "R71")
      (value "270")
      (footprint "eagle-import:0603-RES")
      (libsource (lib "eagle-import") (part "RESISTOR0603-RES"))
    )
    (comp (ref "RESET")
      (value "TAC_SWITCH")
      (footprint "eagle-import:PUSHBUTTON")
      (libsource (lib "eagle-import") (part "TAC_SWITCH"))
    )
    (comp (ref "RESETA")
      (value "TAC_SWITCH")
      (footprint "eagle-import:PUSHBUTTON")
      (libsource (lib "eagle-import") (part "TAC_SWITCH"))
    )
    (comp (ref "SERIAL1")
      (value "M081X08")
      (footprint "eagle-import:1X08")
      (libsource (lib "eagle-import") (part "M081X08"))
    )
    (comp (ref "SERIAL2")
      (value "M04X2")
      (footprint "eagle-import:2X4")
      (libsource (lib "eagle-import") (part "M04X2"))
    )
    (comp (ref "SERIAL3")
      (value "M081X08")
      (footprint "eagle-import:1X08")
      (libsource (lib "eagle-import") (part "M081X08"))
    )
    (comp (ref "SJ1")
      (value "SOLDERJUMPERNO")
      (footprint "eagle-import:SJ_2S-NO")
      (libsource (lib "eagle-import") (part "SOLDERJUMPERNO"))
    )
    (comp (ref "SJ2")
      (value "SOLDERJUMPERNO")
      (footprint "eagle-import:SJ_2S-NO")
      (libsource (lib "eagle-import") (part "SOLDERJUMPERNO"))
    )
    (comp (ref "SSW1")
      (value "SMART_SWITCHSMART_SWITCH_8PIN")
      (footprint "eagle-import:SMART_SWITCH")
      (libsource (lib "eagle-import") (part "SMART_SWITCHSMART_SWITCH_8PIN"))
    )
    (comp (ref "SSW2")
      (value "SMART_SWITCHSMART_SWITCH_8PIN")
      (footprint "eagle-import:SMART_SWITCH")
      (libsource (lib "eagle-import") (part "SMART_SWITCHSMART_SWITCH_8PIN"))
    )
    (comp (ref "SW1")
      (value "EC12E_SW")
      (footprint "eagle-import:ALPS_EC12E_SW")
      (fields (field (name "MPN") "EC12E2424407"))
      (libsource (lib "eagle-import") (part "EC12E_SW"))
    )
    (comp (ref "U$1")
      (value "LEDBICOLOR-AKA")
      (footprint "eagle-import:LED5MM-BICOLOR")
      (libsource (lib "eagle-import") (part "LEDBICOLOR-AKA"))
    )
    (comp (ref "U$7")
      (value "GNDPAD6MM")
      (footprint "eagle-import:3.2MMPAD6MM")
      (libsource (lib "eagle-import") (part "GNDPAD6MM"))
    )
    (comp (ref "U$15")
      (value "GNDPAD6MM")
      (footprint "eagle-import:3.2MMPAD6MM")
      (libsource (lib "eagle-import") (part "GNDPAD6MM"))
    )
    (comp (ref "U$18")
      (value "GNDPAD6MM")
      (footprint "eagle-import:3.2MMPAD6MM")
      (libsource (lib "eagle-import") (part "GNDPAD6MM"))
    )
    (comp (ref "U$20")
      (value "GNDPAD6MM")
      (footprint "eagle-import:3.2MMPAD6MM")
      (libsource (lib "eagle-import") (part "GNDPAD6MM"))
    )
    (comp (ref "U$21")
      (value "GNDPAD6MM")
      (footprint "eagle-import:3.2MMPAD6MM")
      (libsource (lib "eagle-import") (part "GNDPAD6MM"))
    )
    (comp (ref "U$34")
      (value "2BITADDR")
      (footprint "eagle-import:2BITADDR")
      (libsource (lib "eagle-import") (part "2BITADDR"))
    )
    (comp (ref "U$66")
      (value "M02X2")
      (footprint "eagle-import:2X2")
      (libsource (lib "eagle-import") (part "M02X2"))
    )
    (comp (ref "U1")
      (value "ARDUINO-MEGAFULL")
      (footprint "eagle-import:ARDUINO_MEGA")
      (libsource (lib "eagle-import") (part "ARDUINO-MEGAFULL"))
    )
    (comp (ref "UART1")
      (value "M05X2PTH")
      (footprint "eagle-import:AVR_ICSP")
      (libsource (lib "eagle-import") (part "M05X2PTH"))
    )
  )
  (nets
    (net (code "1") (name "5V") (class "Default")
      (node (ref "B1") (pin "COM") (pinfunction "A_COM") (pintype "bidirectional"))
      (node (ref "B10") (pin "COM") (pinfunction "A_COM") (pintype "bidirectional"))
      (node (ref "B10ALT") (pin "COM") (pinfunction "A_COM") (pintype "bidirectional"))
      (node (ref "B11") (pin "COM") (pinfunction "A_COM") (pintype "bidirectional"))
      (node (ref "B11ALT") (pin "COM") (pinfunction "A_COM") (pintype "bidirectional"))
      (node (ref "B12") (pin "COM") (pinfunction "A_COM") (pintype "bidirectional"))
      (node (ref "B12ALT") (pin "COM") (pinfunction "A_COM") (pintype "bidirectional"))
      (node (ref "B13") (pin "COM") (pinfunction "A_COM") (pintype "bidirectional"))
      (node (ref "B14") (pin "COM") (pinfunction "A_COM") (pintype "bidirectional"))
      (node (ref "B14ALT") (pin "COM") (pinfunction "A_COM") (pintype "bidirectional"))
      (node (ref "B15") (pin "COM") (pinfunction "A_COM") (pintype "bidirectional"))
      (node (ref "B16") (pin "COM") (pinfunction "A_COM") (pintype "bidirectional"))
      (node (ref "B17") (pin "COM") (pinfunction "A_COM") (pintype "bidirectional"))
      (node (ref "B17ALT") (pin "COM") (pinfunction "A_COM") (pintype "bidirectional"))
      (node (ref "B18") (pin "COM") (pinfunction "A_COM") (pintype "bidirectional"))
      (node (ref "B19") (pin "COM") (pinfunction "A_COM") (pintype "bidirectional"))
      (node (ref "B1ALT") (pin "COM") (pinfunction "A_COM") (pintype "bidirectional"))
      (node (ref "B2") (pin "COM") (pinfunction "A_COM") (pintype "bidirectional"))
      (node (ref "B20") (pin "COM") (pinfunction "A_COM") (pintype "bidirectional"))
      (node (ref "B20ALT") (pin "COM") (pinfunction "A_COM") (pintype "bidirectional"))
      (node (ref "B21") (pin "COM") (pinfunction "A_COM") (pintype "bidirectional"))
      (node (ref "B21ALT") (pin "COM") (pinfunction "A_COM") (pintype "bidirectional"))
      (node (ref "B22") (pin "COM") (pinfunction "A_COM") (pintype "bidirectional"))
      (node (ref "B23") (pin "COM") (pinfunction "A_COM") (pintype "bidirectional"))
      (node (ref "B24") (pin "COM") (pinfunction "A_COM") (pintype "bidirectional"))
      (node (ref "B25") (pin "COM") (pinfunction "A_COM") (pintype "bidirectional"))
      (node (ref "B26") (pin "COM") (pinfunction "A_COM") (pintype "bidirectional"))
      (node (ref "B26ALT") (pin "COM") (pinfunction "A_COM") (pintype "bidirectional"))
      (node (ref "B27") (pin "COM") (pinfunction "A_COM") (pintype "bidirectional"))
      (node (ref "B27ALT") (pin "COM") (pinfunction "A_COM") (pintype "bidirectional"))
      (node (ref "B28") (pin "COM") (pinfunction "A_COM") (pintype "bidirectional"))
      (node (ref "B29") (pin "COM") (pinfunction "A_COM") (pintype "bidirectional"))
      (node (ref "B2ALT") (pin "COM") (pinfunction "A_COM") (pintype "bidirectional"))
      (node (ref "B3") (pin "COM") (pinfunction "A_COM") (pintype "bidirectional"))
      (node (ref "B30") (pin "COM") (pinfunction "A_COM") (pintype "bidirectional"))
      (node (ref "B3ALT") (pin "COM") (pinfunction "A_COM") (pintype "bidirectional"))
      (node (ref "B4") (pin "COM") (pinfunction "A_COM") (pintype "bidirectional"))
      (node (ref "B4ALT") (pin "COM") (pinfunction "A_COM") (pintype "bidirectional"))
      (node (ref "B5") (pin "COM") (pinfunction "A_COM") (pintype "bidirectional"))
      (node (ref "B5ALT") (pin "COM") (pinfunction "A_COM") (pintype "bidirectional"))
      (node (ref "B6") (pin "COM") (pinfunction "A_COM") (pintype "bidirectional"))
      (node (ref "B6ALT") (pin "COM") (pinfunction "A_COM") (pintype "bidirectional"))
      (node (ref "B7") (pin "COM") (pinfunction "A_COM") (pintype "bidirectional"))
      (node (ref "B7ALT") (pin "COM") (pinfunction "A_COM") (pintype "bidirectional"))
      (node (ref "B8") (pin "COM") (pinfunction "A_COM") (pintype "bidirectional"))
      (node (ref "B8ALT") (pin "COM") (pinfunction "A_COM") (pintype "bidirectional"))
      (node (ref "B9") (pin "COM") (pinfunction "A_COM") (pintype "bidirectional"))
      (node (ref "B9ALT") (pin "COM") (pinfunction "A_COM") (pintype "bidirectional"))
      (node (ref "C10") (pin "1") (pinfunction "1_1") (pintype "passive"))
      (node (ref "C11") (pin "1") (pinfunction "1_1") (pintype "passive"))
      (node (ref "C12") (pin "1") (pinfunction "1_1") (pintype "passive"))
      (node (ref "C13") (pin "1") (pinfunction "1_1") (pintype "passive"))
      (node (ref "C14") (pin "1") (pinfunction "1_1") (pintype "passive"))
      (node (ref "C15") (pin "2") (pinfunction "2_2") (pintype "passive"))
      (node (ref "C16") (pin "1") (pinfunction "1_1") (pintype "passive"))
      (node (ref "C17") (pin "1") (pinfunction "1_1") (pintype "passive"))
      (node (ref "C18") (pin "1") (pinfunction "1_1") (pintype "passive"))
      (node (ref "C19") (pin "1") (pinfunction "1_1") (pintype "passive"))
      (node (ref "C20") (pin "1") (pinfunction "1_1") (pintype "passive"))
      (node (ref "C21") (pin "2") (pinfunction "2_2") (pintype "passive"))
      (node (ref "C22") (pin "1") (pinfunction "1_1") (pintype "passive"))
      (node (ref "C23") (pin "1") (pinfunction "1_1") (pintype "passive"))
      (node (ref "C27") (pin "1") (pinfunction "1_1") (pintype "passive"))
      (node (ref "C30") (pin "2") (pinfunction "2_2") (pintype "passive"))
      (node (ref "C4") (pin "2") (pinfunction "2_2") (pintype "passive"))
      (node (ref "C5") (pin "1") (pinfunction "1_1") (pintype "passive"))
      (node (ref "C7") (pin "1") (pinfunction "1_1") (pintype "passive"))
      (node (ref "C8") (pin "1") (pinfunction "1_1") (pintype "passive"))
      (node (ref "C9") (pin "1") (pinfunction "1_1") (pintype "passive"))
      (node (ref "IC1") (pin "18") (pinfunction "~{RESET}_18") (pintype "input"))
      (node (ref "IC1") (pin "9") (pinfunction "VDD_9") (pintype "power_in"))
      (node (ref "IC2") (pin "24") (pinfunction "A5_24") (pintype "input"))
      (node (ref "IC2") (pin "28") (pinfunction "VDD_28") (pintype "power_in"))
      (node (ref "IC2") (pin "4") (pinfunction "A3_4") (pintype "input"))
      (node (ref "IC2") (pin "5") (pinfunction "A4_5") (pintype "input"))
      (node (ref "IC3") (pin "24") (pinfunction "A5_24") (pintype "input"))
      (node (ref "IC3") (pin "28") (pinfunction "VDD_28") (pintype "power_in"))
      (node (ref "IC4") (pin "1") (pinfunction "A0_1") (pintype "input"))
      (node (ref "IC4") (pin "24") (pinfunction "A5_24") (pintype "input"))
      (node (ref "IC4") (pin "28") (pinfunction "VDD_28") (pintype "power_in"))
      (node (ref "IC4") (pin "4") (pinfunction "A3_4") (pintype "input"))
      (node (ref "IC4") (pin "5") (pinfunction "A4_5") (pintype "input"))
      (node (ref "IC5") (pin "1") (pinfunction "A0_1") (pintype "input"))
      (node (ref "IC5") (pin "24") (pinfunction "A5_24") (pintype "input"))
      (node (ref "IC5") (pin "28") (pinfunction "VDD_28") (pintype "power_in"))
      (node (ref "IC6") (pin "15") (pinfunction "A0_15") (pintype "input"))
      (node (ref "IC6") (pin "18") (pinfunction "~{RESET}_18") (pintype "input"))
      (node (ref "IC6") (pin "9") (pinfunction "VDD_9") (pintype "power_in"))
      (node (ref "IC7") (pin "16") (pinfunction "A1_16") (pintype "input"))
      (node (ref "IC7") (pin "18") (pinfunction "~{RESET}_18") (pintype "input"))
      (node (ref "IC7") (pin "9") (pinfunction "VDD_9") (pintype "power_in"))
      (node (ref "IC8") (pin "15") (pinfunction "A0_15") (pintype "input"))
      (node (ref "IC8") (pin "16") (pinfunction "A1_16") (pintype "input"))
      (node (ref "IC8") (pin "18") (pinfunction "~{RESET}_18") (pintype "input"))
      (node (ref "IC8") (pin "9") (pinfunction "VDD_9") (pintype "power_in"))
      (node (ref "IC9") (pin "14") (pinfunction "VCC_14") (pintype "power_in"))
      (node (ref "JP3") (pin "3") (pinfunction "3_3") (pintype "passive"))
      (node (ref "JP4") (pin "2") (pinfunction "2_2") (pintype "passive"))
      (node (ref "JP4") (pin "3") (pinfunction "3_3") (pintype "passive"))
      (node (ref "L3") (pin "1") (pinfunction "1_1") (pintype "passive"))
      (node (ref "PC2") (pin "+") (pinfunction "+_+") (pintype "passive"))
      (node (ref "POT1") (pin "1") (pinfunction "E_1") (pintype "passive"))
      (node (ref "R58") (pin "2") (pinfunction "2_2") (pintype "passive"))
      (node (ref "R9") (pin "1") (pinfunction "1_1") (pintype "passive"))
      (node (ref "SERIAL1") (pin "2") (pinfunction "2_2") (pintype "passive"))
      (node (ref "SERIAL3") (pin "2") (pinfunction "2_2") (pintype "passive"))
      (node (ref "SSW1") (pin "4") (pinfunction "VDD_4") (pintype "bidirectional"))
      (node (ref "SSW2") (pin "4") (pinfunction "VDD_4") (pintype "bidirectional"))
      (node (ref "U$34") (pin "H2") (pinfunction "VCC_H2") (pintype "passive"))
      (node (ref "U$34") (pin "H3") (pinfunction "VCC_H3") (pintype "passive"))
    )
    (net (code "2") (name "5V_RAW") (class "Default")
      (node (ref "C3") (pin "1") (pinfunction "1_1") (pintype "passive"))
      (node (ref "C6") (pin "1") (pinfunction "1_1") (pintype "passive"))
      (node (ref "L1") (pin "1") (pinfunction "1_1") (pintype "passive"))
      (node (ref "L2") (pin "2") (pinfunction "2_2") (pintype "passive"))
      (node (ref "L3") (pin "2") (pinfunction "2_2") (pintype "passive"))
      (node (ref "L6") (pin "1") (pinfunction "1_1") (pintype "passive"))
      (node (ref "R5") (pin "2") (pinfunction "2_2") (pintype "passive"))
      (node (ref "R6") (pin "2") (pinfunction "2_2") (pintype "passive"))
      (node (ref "U1") (pin "5V@0") (pinfunction "5V_5V@0") (pintype "bidirectional"))
      (node (ref "U1") (pin "5V@1") (pinfunction "5V_5V@1") (pintype "bidirectional"))
      (node (ref "U1") (pin "5V@2") (pinfunction "5V_5V@2") (pintype "bidirectional"))
    )
    (net (code "3") (name "A0") (class "Default")
      (node (ref "JP3") (pin "2") (pinfunction "2_2") (pintype "passive"))
      (node (ref "POT1") (pin "2A") (pinfunction "S_2A") (pintype "passive"))
      (node (ref "SERIAL1") (pin "5") (pinfunction "5_5") (pintype "passive"))
      (node (ref "SERIAL2") (pin "5") (pinfunction "5_5") (pintype "passive"))
      (node (ref "SERIAL3") (pin "5") (pinfunction "5_5") (pintype "passive"))
      (node (ref "U1") (pin "A0") (pinfunction "A0(RX0)_A0") (pintype "bidirectional"))
    )
    (net (code "4") (name "A1") (class "Default")
      (node (ref "CONF-A1") (pin "2") (pinfunction "2_2") (pintype "passive"))
      (node (ref "U1") (pin "A1") (pinfunction "A1(TX0)_A1") (pintype "bidirectional"))
    )
    (net (code "5") (name "A2") (class "Default")
      (node (ref "IC1") (pin "17") (pinfunction "A2_17") (pintype "input"))
      (node (ref "IC2") (pin "3") (pinfunction "A2_3") (pintype "input"))
      (node (ref "IC3") (pin "3") (pinfunction "A2_3") (pintype "input"))
      (node (ref "IC4") (pin "3") (pinfunction "A2_3") (pintype "input"))
      (node (ref "IC5") (pin "3") (pinfunction "A2_3") (pintype "input"))
      (node (ref "IC6") (pin "17") (pinfunction "A2_17") (pintype "input"))
      (node (ref "IC7") (pin "17") (pinfunction "A2_17") (pintype "input"))
      (node (ref "IC8") (pin "17") (pinfunction "A2_17") (pintype "input"))
      (node (ref "U$34") (pin "A2") (pinfunction "A2_A2") (pintype "passive"))
    )
    (net (code "6") (name "A3") (class "Default")
      (node (ref "ANLGDAISY-MAIN") (pin "2") (pinfunction "2_2") (pintype "passive"))
      (node (ref "U1") (pin "A3") (pinfunction "A3_A3") (pintype "bidirectional"))
    )
    (net (code "7") (name "A4") (class "Default")
      (node (ref "ANLGDAISY-MAIN") (pin "3") (pinfunction "3_3") (pintype "passive"))
      (node (ref "U1") (pin "A4") (pinfunction "A4_A4") (pintype "bidirectional"))
    )
    (net (code "8") (name "A5") (class "Default")
      (node (ref "ANLGDAISY-MAIN") (pin "4") (pinfunction "4_4") (pintype "passive"))
      (node (ref "U1") (pin "A5") (pinfunction "A5_A5") (pintype "bidirectional"))
    )
    (net (code "9") (name "A6") (class "Default")
      (node (ref "U1") (pin "A6") (pinfunction "A6_A6") (pintype "bidirectional"))
    )
    (net (code "10") (name "A7") (class "Default")
      (node (ref "U1") (pin "A7") (pinfunction "A7_A7") (pintype "bidirectional"))
    )
    (net (code "11") (name "A8") (class "Default")
      (node (ref "U1") (pin "A8") (pinfunction "A8_A8") (pintype "bidirectional"))
    )
    (net (code "12") (name "A9") (class "Default")
      (node (ref "U1") (pin "A9") (pinfunction "A9_A9") (pintype "bidirectional"))
    )
    (net (code "13") (name "A10") (class "Default")
      (node (ref "U1") (pin "A10") (pinfunction "A10_A10") (pintype "bidirectional"))
    )
    (net (code "14") (name "A11") (class "Default")
      (node (ref "U1") (pin "A11") (pinfunction "A11_A11") (pintype "bidirectional"))
    )
    (net (code "15") (name "A12") (class "Default")
      (node (ref "ANLGDAISY-MAIN") (pin "7") (pinfunction "7_7") (pintype "passive"))
      (node (ref "JOYSTICKS") (pin "2") (pinfunction "2_2") (pintype "passive"))
      (node (ref "U1") (pin "A12") (pinfunction "A12_A12") (pintype "bidirectional"))
    )
    (net (code "16") (name "A13") (class "Default")
      (node (ref "ANLGDAISY-MAIN") (pin "8") (pinfunction "8_8") (pintype "passive"))
      (node (ref "JOYSTICKS") (pin "3") (pinfunction "3_3") (pintype "passive"))
      (node (ref "U1") (pin "A13") (pinfunction "A13_A13") (pintype "bidirectional"))
    )
    (net (code "17") (name "A14") (class "Default")
      (node (ref "ANLGDAISY-MAIN") (pin "5") (pinfunction "5_5") (pintype "passive"))
      (node (ref "JOYSTICKS") (pin "5") (pinfunction "5_5") (pintype "passive"))
      (node (ref "U1") (pin "A14") (pinfunction "A14_A14") (pintype "bidirectional"))
    )
    (net (code "18") (name "A15") (class "Default")
      (node (ref "ANLGDAISY-MAIN") (pin "6") (pinfunction "6_6") (pintype "passive"))
      (node (ref "JOYSTICKS") (pin "6") (pinfunction "6_6") (pintype "passive"))
      (node (ref "U1") (pin "A15") (pinfunction "A15_A15") (pintype "bidirectional"))
    )
    (net (code "19") (name "AD0") (class "Default")
      (node (ref "C26") (pin "1") (pinfunction "1_1") (pintype "passive"))
      (node (ref "IC8") (pin "1") (pinfunction "GPB0_1") (pintype "bidirectional"))
      (node (ref "SW1") (pin "E") (pinfunction "2_E") (pintype "passive"))
      (node (ref "U$66") (pin "4") (pinfunction "4_4") (pintype "passive"))
    )
    (net (code "20") (name "AN2") (class "Default")
      (node (ref "ANLGDAISY-MAIN") (pin "1") (pinfunction "1_1") (pintype "passive"))
      (node (ref "U1") (pin "A2") (pinfunction "A2_A2") (pintype "bidirectional"))
    )
    (net (code "21") (name "D2") (class "Default")
      (node (ref "IC8") (pin "21") (pinfunction "GPA0_21") (pintype "bidirectional"))
      (node (ref "IC9") (pin "12") (pinfunction "O_12") (pintype "output"))
    )
    (net (code "22") (name "D3") (class "Default")
      (node (ref "C25") (pin "1") (pinfunction "1_1") (pintype "passive"))
      (node (ref "IC8") (pin "22") (pinfunction "GPA1_22") (pintype "bidirectional"))
      (node (ref "SW1") (pin "A") (pinfunction "A_A") (pintype "passive"))
      (node (ref "U$66") (pin "3") (pinfunction "3_3") (pintype "passive"))
    )
    (net (code "23") (name "D6") (class "Default")
      (node (ref "U1") (pin "6") (pinfunction "6_6") (pintype "bidirectional"))
    )
    (net (code "24") (name "D7") (class "Default")
      (node (ref "U1") (pin "7") (pinfunction "7_7") (pintype "bidirectional"))
    )
    (net (code "25") (name "D8") (class "Default")
      (node (ref "U1") (pin "8") (pinfunction "8_8") (pintype "bidirectional"))
    )
    (net (code "26") (name "D9") (class "Default")
      (node (ref "U1") (pin "9") (pinfunction "9_9") (pintype "bidirectional"))
    )
    (net (code "27") (name "D22") (class "Default")
      (node (ref "R7") (pin "2") (pinfunction "2_2") (pintype "passive"))
      (node (ref "U1") (pin "22") (pinfunction "22_22") (pintype "bidirectional"))
    )
    (net (code "28") (name "D23") (class "Default")
      (node (ref "R8") (pin "2") (pinfunction "2_2") (pintype "passive"))
      (node (ref "U1") (pin "23") (pinfunction "23_23") (pintype "bidirectional"))
    )
    (net (code "29") (name "D24") (class "Default")
      (node (ref "U1") (pin "24") (pinfunction "24_24") (pintype "bidirectional"))
    )
    (net (code "30") (name "D37") (class "Default")
      (node (ref "CONF") (pin "3") (pinfunction "3_3") (pintype "passive"))
      (node (ref "CONF-A1") (pin "1") (pinfunction "1_1") (pintype "passive"))
      (node (ref "R9") (pin "2") (pinfunction "2_2") (pintype "passive"))
      (node (ref "U1") (pin "37") (pinfunction "37_37") (pintype "bidirectional"))
    )
    (net (code "31") (name "EXT1") (class "Default")
      (node (ref "U1") (pin "25") (pinfunction "25_25") (pintype "bidirectional"))
    )
    (net (code "32") (name "EXT2") (class "Default")
      (node (ref "U1") (pin "26") (pinfunction "26_26") (pintype "bidirectional"))
    )
    (net (code "33") (name "EXT3") (class "Default")
      (node (ref "U1") (pin "27") (pinfunction "27_27") (pintype "bidirectional"))
    )
    (net (code "34") (name "EXT4") (class "Default")
      (node (ref "U1") (pin "28") (pinfunction "28_28") (pintype "bidirectional"))
    )
    (net (code "35") (name "EXT5") (class "Default")
      (node (ref "U1") (pin "29") (pinfunction "29_29") (pintype "bidirectional"))
    )
    (net (code "36") (name "EXT6") (class "Default")
      (node (ref "U1") (pin "30") (pinfunction "30_30") (pintype "bidirectional"))
    )
    (net (code "37") (name "EXT7") (class "Default")
      (node (ref "U1") (pin "31") (pinfunction "31_31") (pintype "bidirectional"))
    )
    (net (code "38") (name "EXT8") (class "Default")
      (node (ref "U1") (pin "32") (pinfunction "32_32") (pintype "bidirectional"))
    )
    (net (code "39") (name "GND") (class "Default")
      (node (ref "B1") (pin "P$4") (pinfunction "SW1_P$4") (pintype "bidirectional"))
      (node (ref "B10") (pin "P$4") (pinfunction "SW1_P$4") (pintype "bidirectional"))
      (node (ref "B10ALT") (pin "P$4") (pinfunction "SW1_P$4") (pintype "bidirectional"))
      (node (ref "B11") (pin "P$4") (pinfunction "SW1_P$4") (pintype "bidirectional"))
      (node (ref "B11ALT") (pin "P$4") (pinfunction "SW1_P$4") (pintype "bidirectional"))
      (node (ref "B12") (pin "P$4") (pinfunction "SW1_P$4") (pintype "bidirectional"))
      (node (ref "B12ALT") (pin "P$4") (pinfunction "SW1_P$4") (pintype "bidirectional"))
      (node (ref "B13") (pin "P$4") (pinfunction "SW1_P$4") (pintype "bidirectional"))
      (node (ref "B14") (pin "P$4") (pinfunction "SW1_P$4") (pintype "bidirectional"))
      (node (ref "B14ALT") (pin "P$4") (pinfunction "SW1_P$4") (pintype "bidirectional"))
      (node (ref "B15") (pin "P$4") (pinfunction "SW1_P$4") (pintype "bidirectional"))
      (node (ref "B16") (pin "P$4") (pinfunction "SW1_P$4") (pintype "bidirectional"))
      (node (ref "B17") (pin "P$4") (pinfunction "SW1_P$4") (pintype "bidirectional"))
      (node (ref "B17ALT") (pin "P$4") (pinfunction "SW1_P$4") (pintype "bidirectional"))
      (node (ref "B18") (pin "P$4") (pinfunction "SW1_P$4") (pintype "bidirectional"))
      (node (ref "B19") (pin "P$4") (pinfunction "SW1_P$4") (pintype "bidirectional"))
      (node (ref "B1ALT") (pin "P$4") (pinfunction "SW1_P$4") (pintype "bidirectional"))
      (node (ref "B2") (pin "P$4") (pinfunction "SW1_P$4") (pintype "bidirectional"))
      (node (ref "B20") (pin "P$4") (pinfunction "SW1_P$4") (pintype "bidirectional"))
      (node (ref "B20ALT") (pin "P$4") (pinfunction "SW1_P$4") (pintype "bidirectional"))
      (node (ref "B21") (pin "P$4") (pinfunction "SW1_P$4") (pintype "bidirectional"))
      (node (ref "B21ALT") (pin "P$4") (pinfunction "SW1_P$4") (pintype "bidirectional"))
      (node (ref "B22") (pin "P$4") (pinfunction "SW1_P$4") (pintype "bidirectional"))
      (node (ref "B23") (pin "P$4") (pinfunction "SW1_P$4") (pintype "bidirectional"))
      (node (ref "B24") (pin "P$4") (pinfunction "SW1_P$4") (pintype "bidirectional"))
      (node (ref "B25") (pin "P$4") (pinfunction "SW1_P$4") (pintype "bidirectional"))
      (node (ref "B26") (pin "P$4") (pinfunction "SW1_P$4") (pintype "bidirectional"))
      (node (ref "B26ALT") (pin "P$4") (pinfunction "SW1_P$4") (pintype "bidirectional"))
      (node (ref "B27") (pin "P$4") (pinfunction "SW1_P$4") (pintype "bidirectional"))
      (node (ref "B27ALT") (pin "P$4") (pinfunction "SW1_P$4") (pintype "bidirectional"))
      (node (ref "B28") (pin "P$4") (pinfunction "SW1_P$4") (pintype "bidirectional"))
      (node (ref "B29") (pin "P$4") (pinfunction "SW1_P$4") (pintype "bidirectional"))
      (node (ref "B2ALT") (pin "P$4") (pinfunction "SW1_P$4") (pintype "bidirectional"))
      (node (ref "B3") (pin "P$4") (pinfunction "SW1_P$4") (pintype "bidirectional"))
      (node (ref "B30") (pin "P$4") (pinfunction "SW1_P$4") (pintype "bidirectional"))
      (node (ref "B3ALT") (pin "P$4") (pinfunction "SW1_P$4") (pintype "bidirectional"))
      (node (ref "B4") (pin "P$4") (pinfunction "SW1_P$4") (pintype "bidirectional"))
      (node (ref "B4ALT") (pin "P$4") (pinfunction "SW1_P$4") (pintype "bidirectional"))
      (node (ref "B5") (pin "P$4") (pinfunction "SW1_P$4") (pintype "bidirectional"))
      (node (ref "B5ALT") (pin "P$4") (pinfunction "SW1_P$4") (pintype "bidirectional"))
      (node (ref "B6") (pin "P$4") (pinfunction "SW1_P$4") (pintype "bidirectional"))
      (node (ref "B6ALT") (pin "P$4") (pinfunction "SW1_P$4") (pintype "bidirectional"))
      (node (ref "B7") (pin "P$4") (pinfunction "SW1_P$4") (pintype "bidirectional"))
      (node (ref "B7ALT") (pin "P$4") (pinfunction "SW1_P$4") (pintype "bidirectional"))
      (node (ref "B8") (pin "P$4") (pinfunction "SW1_P$4") (pintype "bidirectional"))
      (node (ref "B8ALT") (pin "P$4") (pinfunction "SW1_P$4") (pintype "bidirectional"))
      (node (ref "B9") (pin "P$4") (pinfunction "SW1_P$4") (pintype "bidirectional"))
      (node (ref "B9ALT") (pin "P$4") (pinfunction "SW1_P$4") (pintype "bidirectional"))
      (node (ref "C1") (pin "2") (pinfunction "2_2") (pintype "passive"))
      (node (ref "C10") (pin "2") (pinfunction "2_2") (pintype "passive"))
      (node (ref "C11") (pin "2") (pinfunction "2_2") (pintype "passive"))
      (node (ref "C12") (pin "2") (pinfunction "2_2") (pintype "passive"))
      (node (ref "C13") (pin "2") (pinfunction "2_2") (pintype "passive"))
      (node (ref "C14") (pin "2") (pinfunction "2_2") (pintype "passive"))
      (node (ref "C15") (pin "1") (pinfunction "1_1") (pintype "passive"))
      (node (ref "C16") (pin "2") (pinfunction "2_2") (pintype "passive"))
      (node (ref "C17") (pin "2") (pinfunction "2_2") (pintype "passive"))
      (node (ref "C18") (pin "2") (pinfunction "2_2") (pintype "passive"))
      (node (ref "C19") (pin "2") (pinfunction "2_2") (pintype "passive"))
      (node (ref "C2") (pin "2") (pinfunction "2_2") (pintype "passive"))
      (node (ref "C20") (pin "2") (pinfunction "2_2") (pintype "passive"))
      (node (ref "C21") (pin "1") (pinfunction "1_1") (pintype "passive"))
      (node (ref "C22") (pin "2") (pinfunction "2_2") (pintype "passive"))
      (node (ref "C23") (pin "2") (pinfunction "2_2") (pintype "passive"))
      (node (ref "C24") (pin "2") (pinfunction "2_2") (pintype "passive"))
      (node (ref "C25") (pin "2") (pinfunction "2_2") (pintype "passive"))
      (node (ref "C26") (pin "2") (pinfunction "2_2") (pintype "passive"))
      (node (ref "C27") (pin "2") (pinfunction "2_2") (pintype "passive"))
      (node (ref "C3") (pin "2") (pinfunction "2_2") (pintype "passive"))
      (node (ref "C30") (pin "1") (pinfunction "1_1") (pintype "passive"))
      (node (ref "C4") (pin "1") (pinfunction "1_1") (pintype "passive"))
      (node (ref "C5") (pin "2") (pinfunction "2_2") (pintype "passive"))
      (node (ref "C6") (pin "2") (pinfunction "2_2") (pintype "passive"))
      (node (ref "C7") (pin "2") (pinfunction "2_2") (pintype "passive"))
      (node (ref "C8") (pin "2") (pinfunction "2_2") (pintype "passive"))
      (node (ref "C9") (pin "2") (pinfunction "2_2") (pintype "passive"))
      (node (ref "CONF") (pin "1") (pinfunction "1_1") (pintype "passive"))
      (node (ref "IC1") (pin "10") (pinfunction "VSS_10") (pintype "power_in"))
      (node (ref "IC1") (pin "15") (pinfunction "A0_15") (pintype "input"))
      (node (ref "IC1") (pin "16") (pinfunction "A1_16") (pintype "input"))
      (node (ref "IC2") (pin "1") (pinfunction "A0_1") (pintype "input"))
      (node (ref "IC2") (pin "14") (pinfunction "GND_14") (pintype "power_in"))
      (node (ref "IC2") (pin "2") (pinfunction "A1_2") (pintype "input"))
      (node (ref "IC2") (pin "23") (pinfunction "OE_23") (pintype "input"))
      (node (ref "IC2") (pin "25") (pinfunction "EXTCLK_25") (pintype "input"))
      (node (ref "IC3") (pin "1") (pinfunction "A0_1") (pintype "input"))
      (node (ref "IC3") (pin "14") (pinfunction "GND_14") (pintype "power_in"))
      (node (ref "IC3") (pin "2") (pinfunction "A1_2") (pintype "input"))
      (node (ref "IC3") (pin "23") (pinfunction "OE_23") (pintype "input"))
      (node (ref "IC3") (pin "25") (pinfunction "EXTCLK_25") (pintype "input"))
      (node (ref "IC3") (pin "4") (pinfunction "A3_4") (pintype "input"))
      (node (ref "IC3") (pin "5") (pinfunction "A4_5") (pintype "input"))
      (node (ref "IC4") (pin "14") (pinfunction "GND_14") (pintype "power_in"))
      (node (ref "IC4") (pin "2") (pinfunction "A1_2") (pintype "input"))
      (node (ref "IC4") (pin "23") (pinfunction "OE_23") (pintype "input"))
      (node (ref "IC4") (pin "25") (pinfunction "EXTCLK_25") (pintype "input"))
      (node (ref "IC5") (pin "14") (pinfunction "GND_14") (pintype "power_in"))
      (node (ref "IC5") (pin "2") (pinfunction "A1_2") (pintype "input"))
      (node (ref "IC5") (pin "23") (pinfunction "OE_23") (pintype "input"))
      (node (ref "IC5") (pin "25") (pinfunction "EXTCLK_25") (pintype "input"))
      (node (ref "IC5") (pin "4") (pinfunction "A3_4") (pintype "input"))
      (node (ref "IC5") (pin "5") (pinfunction "A4_5") (pintype "input"))
      (node (ref "IC6") (pin "10") (pinfunction "VSS_10") (pintype "power_in"))
      (node (ref "IC6") (pin "16") (pinfunction "A1_16") (pintype "input"))
      (node (ref "IC7") (pin "10") (pinfunction "VSS_10") (pintype "power_in"))
      (node (ref "IC7") (pin "15") (pinfunction "A0_15") (pintype "input"))
      (node (ref "IC8") (pin "10") (pinfunction "VSS_10") (pintype "power_in"))
      (node (ref "IC9") (pin "1") (pinfunction "I_1") (pintype "input"))
      (node (ref "IC9") (pin "11") (pinfunction "I_11") (pintype "input"))
      (node (ref "IC9") (pin "3") (pinfunction "I_3") (pintype "input"))
      (node (ref "IC9") (pin "5") (pinfunction "I_5") (pintype "input"))
      (node (ref "IC9") (pin "7") (pinfunction "GND_7") (pintype "power_in"))
      (node (ref "IC9") (pin "9") (pinfunction "I_9") (pintype "input"))
      (node (ref "JOYSTICKS") (pin "8") (pinfunction "8_8") (pintype "passive"))
      (node (ref "JP3") (pin "1") (pinfunction "1_1") (pintype "passive"))
      (node (ref "JP3") (pin "4") (pinfunction "4_4") (pintype "passive"))
      (node (ref "JP4") (pin "1") (pinfunction "1_1") (pintype "passive"))
      (node (ref "JP4") (pin "4") (pinfunction "4_4") (pintype "passive"))
      (node (ref "PC2") (pin "-") (pinfunction "-_-") (pintype "passive"))
      (node (ref "POT1") (pin "3") (pinfunction "A_3") (pintype "passive"))
      (node (ref "RESET") (pin "1") (pinfunction "1_1") (pintype "passive"))
      (node (ref "RESETA") (pin "1") (pinfunction "1_1") (pintype "passive"))
      (node (ref "SERIAL1") (pin "1") (pinfunction "1_1") (pintype "passive"))
      (node (ref "SERIAL2") (pin "1") (pinfunction "1_1") (pintype "passive"))
      (node (ref "SERIAL3") (pin "1") (pinfunction "1_1") (pintype "passive"))
      (node (ref "SSW1") (pin "1") (pinfunction "SW1_1") (pintype "bidirectional"))
      (node (ref "SSW1") (pin "3") (pinfunction "GND_3") (pintype "bidirectional"))
      (node (ref "SSW2") (pin "1") (pinfunction "SW1_1") (pintype "bidirectional"))
      (node (ref "SSW2") (pin "3") (pinfunction "GND_3") (pintype "bidirectional"))
      (node (ref "SW1") (pin "C") (pinfunction "C_C") (pintype "passive"))
      (node (ref "SW1") (pin "D") (pinfunction "1_D") (pintype "passive"))
      (node (ref "U$1") (pin "K1") (pinfunction "P$1_K1") (pintype "bidirectional"))
      (node (ref "U$15") (pin "P$1") (pinfunction "1_P$1") (pintype "passive"))
      (node (ref "U$18") (pin "P$1") (pinfunction "1_P$1") (pintype "passive"))
      (node (ref "U$20") (pin "P$1") (pinfunction "1_P$1") (pintype "passive"))
      (node (ref "U$21") (pin "P$1") (pinfunction "1_P$1") (pintype "passive"))
      (node (ref "U$34") (pin "L2") (pinfunction "GND_L2") (pintype "passive"))
      (node (ref "U$34") (pin "L3") (pinfunction "GND_L3") (pintype "passive"))
      (node (ref "U$66") (pin "1") (pinfunction "1_1") (pintype "passive"))
      (node (ref "U$7") (pin "P$1") (pinfunction "1_P$1") (pintype "passive"))
      (node (ref "U1") (pin "GND@0") (pinfunction "GND_GND@0") (pintype "bidirectional"))
      (node (ref "U1") (pin "GND@1") (pinfunction "GND_GND@1") (pintype "bidirectional"))
      (node (ref "U1") (pin "GND@2") (pinfunction "GND_GND@2") (pintype "bidirectional"))
      (node (ref "U1") (pin "GND@3") (pinfunction "GND_GND@3") (pintype "bidirectional"))
      (node (ref "U1") (pin "GND@4") (pinfunction "GND_GND@4") (pintype "bidirectional"))
      (node (ref "UART1") (pin "5") (pinfunction "5_5") (pintype "passive"))
    )
    (net (code "40") (name "GPA0") (class "Default")
      (node (ref "B8") (pin "P$5") (pinfunction "SW2_P$5") (pintype "bidirectional"))
      (node (ref "B8ALT") (pin "P$5") (pinfunction "SW2_P$5") (pintype "bidirectional"))
      (node (ref "IC1") (pin "21") (pinfunction "GPA0_21") (pintype "bidirectional"))
    )
    (net (code "41") (name "GPA0_2") (class "Default")
      (node (ref "IC7") (pin "21") (pinfunction "GPA0_21") (pintype "bidirectional"))
      (node (ref "SSW1") (pin "2") (pinfunction "SW2_2") (pintype "bidirectional"))
    )
    (net (code "42") (name "GPA1") (class "Default")
      (node (ref "B7") (pin "P$5") (pinfunction "SW2_P$5") (pintype "bidirectional"))
      (node (ref "B7ALT") (pin "P$5") (pinfunction "SW2_P$5") (pintype "bidirectional"))
      (node (ref "IC1") (pin "22") (pinfunction "GPA1_22") (pintype "bidirectional"))
    )
    (net (code "43") (name "GPA1_2") (class "Default")
      (node (ref "IC7") (pin "22") (pinfunction "GPA1_22") (pintype "bidirectional"))
      (node (ref "SSW2") (pin "2") (pinfunction "SW2_2") (pintype "bidirectional"))
    )
    (net (code "44") (name "GPA2") (class "Default")
      (node (ref "B6") (pin "P$5") (pinfunction "SW2_P$5") (pintype "bidirectional"))
      (node (ref "B6ALT") (pin "P$5") (pinfunction "SW2_P$5") (pintype "bidirectional"))
      (node (ref "IC1") (pin "23") (pinfunction "GPA2_23") (pintype "bidirectional"))
    )
    (net (code "45") (name "GPA3") (class "Default")
      (node (ref "B5") (pin "P$5") (pinfunction "SW2_P$5") (pintype "bidirectional"))
      (node (ref "B5ALT") (pin "P$5") (pinfunction "SW2_P$5") (pintype "bidirectional"))
      (node (ref "IC1") (pin "24") (pinfunction "GPA3_24") (pintype "bidirectional"))
    )
    (net (code "46") (name "GPA4") (class "Default")
      (node (ref "B1") (pin "P$5") (pinfunction "SW2_P$5") (pintype "bidirectional"))
      (node (ref "B1ALT") (pin "P$5") (pinfunction "SW2_P$5") (pintype "bidirectional"))
      (node (ref "IC1") (pin "25") (pinfunction "GPA4_25") (pintype "bidirectional"))
    )
    (net (code "47") (name "GPA5") (class "Default")
      (node (ref "B2") (pin "P$5") (pinfunction "SW2_P$5") (pintype "bidirectional"))
      (node (ref "B2ALT") (pin "P$5") (pinfunction "SW2_P$5") (pintype "bidirectional"))
      (node (ref "IC1") (pin "26") (pinfunction "GPA5_26") (pintype "bidirectional"))
    )
    (net (code "48") (name "GPA6") (class "Default")
      (node (ref "B3") (pin "P$5") (pinfunction "SW2_P$5") (pintype "bidirectional"))
      (node (ref "B3ALT") (pin "P$5") (pinfunction "SW2_P$5") (pintype "bidirectional"))
      (node (ref "IC1") (pin "27") (pinfunction "GPA6_27") (pintype "bidirectional"))
    )
    (net (code "49") (name "GPA7") (class "Default")
      (node (ref "B4") (pin "P$5") (pinfunction "SW2_P$5") (pintype "bidirectional"))
      (node (ref "B4ALT") (pin "P$5") (pinfunction "SW2_P$5") (pintype "bidirectional"))
      (node (ref "IC1") (pin "28") (pinfunction "GPA7_28") (pintype "bidirectional"))
    )
    (net (code "50") (name "GPA8") (class "Default")
      (node (ref "B16") (pin "P$5") (pinfunction "SW2_P$5") (pintype "bidirectional"))
      (node (ref "IC1") (pin "1") (pinfunction "GPB0_1") (pintype "bidirectional"))
    )
    (net (code "51") (name "GPA9") (class "Default")
      (node (ref "B15") (pin "P$5") (pinfunction "SW2_P$5") (pintype "bidirectional"))
      (node (ref "IC1") (pin "2") (pinfunction "GPB1_2") (pintype "bidirectional"))
    )
    (net (code "52") (name "GPA10") (class "Default")
      (node (ref "B14") (pin "P$5") (pinfunction "SW2_P$5") (pintype "bidirectional"))
      (node (ref "B14ALT") (pin "P$5") (pinfunction "SW2_P$5") (pintype "bidirectional"))
      (node (ref "IC1") (pin "3") (pinfunction "GPB2_3") (pintype "bidirectional"))
    )
    (net (code "53") (name "GPA11") (class "Default")
      (node (ref "B13") (pin "P$5") (pinfunction "SW2_P$5") (pintype "bidirectional"))
      (node (ref "IC1") (pin "4") (pinfunction "GPB3_4") (pintype "bidirectional"))
    )
    (net (code "54") (name "GPA12") (class "Default")
      (node (ref "B9") (pin "P$5") (pinfunction "SW2_P$5") (pintype "bidirectional"))
      (node (ref "B9ALT") (pin "P$5") (pinfunction "SW2_P$5") (pintype "bidirectional"))
      (node (ref "IC1") (pin "5") (pinfunction "GPB4_5") (pintype "bidirectional"))
    )
    (net (code "55") (name "GPA13") (class "Default")
      (node (ref "B10") (pin "P$5") (pinfunction "SW2_P$5") (pintype "bidirectional"))
      (node (ref "B10ALT") (pin "P$5") (pinfunction "SW2_P$5") (pintype "bidirectional"))
      (node (ref "IC1") (pin "6") (pinfunction "GPB5_6") (pintype "bidirectional"))
    )
    (net (code "56") (name "GPA14") (class "Default")
      (node (ref "B11") (pin "P$5") (pinfunction "SW2_P$5") (pintype "bidirectional"))
      (node (ref "B11ALT") (pin "P$5") (pinfunction "SW2_P$5") (pintype "bidirectional"))
      (node (ref "IC1") (pin "7") (pinfunction "GPB6_7") (pintype "bidirectional"))
    )
    (net (code "57") (name "GPA15") (class "Default")
      (node (ref "B12") (pin "P$5") (pinfunction "SW2_P$5") (pintype "bidirectional"))
      (node (ref "B12ALT") (pin "P$5") (pinfunction "SW2_P$5") (pintype "bidirectional"))
      (node (ref "IC1") (pin "8") (pinfunction "GPB7_8") (pintype "bidirectional"))
    )
    (net (code "58") (name "GPA16") (class "Default")
      (node (ref "B24") (pin "P$5") (pinfunction "SW2_P$5") (pintype "bidirectional"))
      (node (ref "IC6") (pin "21") (pinfunction "GPA0_21") (pintype "bidirectional"))
    )
    (net (code "59") (name "GPA17") (class "Default")
      (node (ref "B23") (pin "P$5") (pinfunction "SW2_P$5") (pintype "bidirectional"))
      (node (ref "IC6") (pin "22") (pinfunction "GPA1_22") (pintype "bidirectional"))
    )
    (net (code "60") (name "GPA18") (class "Default")
      (node (ref "B22") (pin "P$5") (pinfunction "SW2_P$5") (pintype "bidirectional"))
      (node (ref "IC6") (pin "23") (pinfunction "GPA2_23") (pintype "bidirectional"))
    )
    (net (code "61") (name "GPA19") (class "Default")
      (node (ref "B21") (pin "P$5") (pinfunction "SW2_P$5") (pintype "bidirectional"))
      (node (ref "B21ALT") (pin "P$5") (pinfunction "SW2_P$5") (pintype "bidirectional"))
      (node (ref "IC6") (pin "24") (pinfunction "GPA3_24") (pintype "bidirectional"))
    )
    (net (code "62") (name "GPA20") (class "Default")
      (node (ref "B17") (pin "P$5") (pinfunction "SW2_P$5") (pintype "bidirectional"))
      (node (ref "B17ALT") (pin "P$5") (pinfunction "SW2_P$5") (pintype "bidirectional"))
      (node (ref "IC6") (pin "25") (pinfunction "GPA4_25") (pintype "bidirectional"))
    )
    (net (code "63") (name "GPA21") (class "Default")
      (node (ref "B18") (pin "P$5") (pinfunction "SW2_P$5") (pintype "bidirectional"))
      (node (ref "IC6") (pin "26") (pinfunction "GPA5_26") (pintype "bidirectional"))
    )
    (net (code "64") (name "GPA22") (class "Default")
      (node (ref "B19") (pin "P$5") (pinfunction "SW2_P$5") (pintype "bidirectional"))
      (node (ref "IC6") (pin "27") (pinfunction "GPA6_27") (pintype "bidirectional"))
    )
    (net (code "65") (name "GPA23") (class "Default")
      (node (ref "B20") (pin "P$5") (pinfunction "SW2_P$5") (pintype "bidirectional"))
      (node (ref "B20ALT") (pin "P$5") (pinfunction "SW2_P$5") (pintype "bidirectional"))
      (node (ref "IC6") (pin "28") (pinfunction "GPA7_28") (pintype "bidirectional"))
    )
    (net (code "66") (name "GPA24") (class "Default")
      (node (ref "IC6") (pin "1") (pinfunction "GPB0_1") (pintype "bidirectional"))
    )
    (net (code "67") (name "GPA25") (class "Default")
      (node (ref "IC6") (pin "2") (pinfunction "GPB1_2") (pintype "bidirectional"))
    )
    (net (code "68") (name "GPA26") (class "Default")
      (node (ref "B30") (pin "P$5") (pinfunction "SW2_P$5") (pintype "bidirectional"))
      (node (ref "IC6") (pin "3") (pinfunction "GPB2_3") (pintype "bidirectional"))
    )
    (net (code "69") (name "GPA27") (class "Default")
      (node (ref "B29") (pin "P$5") (pinfunction "SW2_P$5") (pintype "bidirectional"))
      (node (ref "IC6") (pin "4") (pinfunction "GPB3_4") (pintype "bidirectional"))
    )
    (net (code "70") (name "GPA28") (class "Default")
      (node (ref "B25") (pin "P$5") (pinfunction "SW2_P$5") (pintype "bidirectional"))
      (node (ref "IC6") (pin "5") (pinfunction "GPB4_5") (pintype "bidirectional"))
    )
    (net (code "71") (name "GPA29") (class "Default")
      (node (ref "B26") (pin "P$5") (pinfunction "SW2_P$5") (pintype "bidirectional"))
      (node (ref "B26ALT") (pin "P$5") (pinfunction "SW2_P$5") (pintype "bidirectional"))
      (node (ref "IC6") (pin "6") (pinfunction "GPB5_6") (pintype "bidirectional"))
    )
    (net (code "72") (name "GPA30") (class "Default")
      (node (ref "B27") (pin "P$5") (pinfunction "SW2_P$5") (pintype "bidirectional"))
      (node (ref "B27ALT") (pin "P$5") (pinfunction "SW2_P$5") (pintype "bidirectional"))
      (node (ref "IC6") (pin "7") (pinfunction "GPB6_7") (pintype "bidirectional"))
    )
    (net (code "73") (name "GPA31") (class "Default")
      (node (ref "B28") (pin "P$5") (pinfunction "SW2_P$5") (pintype "bidirectional"))
      (node (ref "IC6") (pin "8") (pinfunction "GPB7_8") (pintype "bidirectional"))
    )
    (net (code "74") (name "GPB0") (class "Default")
      (node (ref "IC7") (pin "1") (pinfunction "GPB0_1") (pintype "bidirectional"))
      (node (ref "SSW1") (pin "8") (pinfunction "SS_8") (pintype "bidirectional"))
    )
    (net (code "75") (name "GPB1") (class "Default")
      (node (ref "IC7") (pin "2") (pinfunction "GPB1_2") (pintype "bidirectional"))
      (node (ref "SSW2") (pin "8") (pinfunction "SS_8") (pintype "bidirectional"))
    )
    (net (code "76") (name "GPIO1-1") (class "Default")
      (node (ref "U1") (pin "33") (pinfunction "33_33") (pintype "bidirectional"))
    )
    (net (code "77") (name "GPIO1-2") (class "Default")
      (node (ref "U1") (pin "34") (pinfunction "34_34") (pintype "bidirectional"))
    )
    (net (code "78") (name "GPIO2-1") (class "Default")
      (node (ref "U1") (pin "38") (pinfunction "38_38") (pintype "bidirectional"))
    )
    (net (code "79") (name "GPIO2-2") (class "Default")
      (node (ref "U1") (pin "39") (pinfunction "39_39") (pintype "bidirectional"))
    )
    (net (code "80") (name "GPIO3-1") (class "Default")
      (node (ref "U1") (pin "40") (pinfunction "40_40") (pintype "bidirectional"))
    )
    (net (code "81") (name "GPIO3-2") (class "Default")
      (node (ref "U1") (pin "41") (pinfunction "41_41") (pintype "bidirectional"))
    )
    (net (code "82") (name "I2C_SCL") (class "Default")
      (node (ref "IC1") (pin "12") (pinfunction "SCL_12") (pintype "input"))
      (node (ref "IC2") (pin "26") (pinfunction "SCL_26") (pintype "input"))
      (node (ref "IC3") (pin "26") (pinfunction "SCL_26") (pintype "input"))
      (node (ref "IC4") (pin "26") (pinfunction "SCL_26") (pintype "input"))
      (node (ref "IC5") (pin "26") (pinfunction "SCL_26") (pintype "input"))
      (node (ref "IC6") (pin "12") (pinfunction "SCL_12") (pintype "input"))
      (node (ref "IC7") (pin "12") (pinfunction "SCL_12") (pintype "input"))
      (node (ref "IC8") (pin "12") (pinfunction "SCL_12") (pintype "input"))
      (node (ref "R5") (pin "1") (pinfunction "1_1") (pintype "passive"))
      (node (ref "SERIAL1") (pin "4") (pinfunction "4_4") (pintype "passive"))
      (node (ref "SERIAL2") (pin "4") (pinfunction "4_4") (pintype "passive"))
      (node (ref "SERIAL3") (pin "4") (pinfunction "4_4") (pintype "passive"))
      (node (ref "U1") (pin "21") (pinfunction "21(SCL)_21") (pintype "bidirectional"))
    )
    (net (code "83") (name "I2C_SDA") (class "Default")
      (node (ref "IC1") (pin "13") (pinfunction "SDA_13") (pintype "bidirectional"))
      (node (ref "IC2") (pin "27") (pinfunction "SDA_27") (pintype "input"))
      (node (ref "IC3") (pin "27") (pinfunction "SDA_27") (pintype "input"))
      (node (ref "IC4") (pin "27") (pinfunction "SDA_27") (pintype "input"))
      (node (ref "IC5") (pin "27") (pinfunction "SDA_27") (pintype "input"))
      (node (ref "IC6") (pin "13") (pinfunction "SDA_13") (pintype "bidirectional"))
      (node (ref "IC7") (pin "13") (pinfunction "SDA_13") (pintype "bidirectional"))
      (node (ref "IC8") (pin "13") (pinfunction "SDA_13") (pintype "bidirectional"))
      (node (ref "R6") (pin "1") (pinfunction "1_1") (pintype "passive"))
      (node (ref "SERIAL1") (pin "3") (pinfunction "3_3") (pintype "passive"))
      (node (ref "SERIAL2") (pin "3") (pinfunction "3_3") (pintype "passive"))
      (node (ref "SERIAL3") (pin "3") (pinfunction "3_3") (pintype "passive"))
      (node (ref "U1") (pin "20") (pinfunction "20(SDA)_20") (pintype "bidirectional"))
    )
    (net (code "84") (name "L0") (class "Default")
      (node (ref "B1") (pin "P$2") (pinfunction "K1_P$2") (pintype "bidirectional"))
      (node (ref "B1ALT") (pin "P$2") (pinfunction "K1_P$2") (pintype "bidirectional"))
      (node (ref "R23") (pin "1") (pinfunction "1_1") (pintype "passive"))
    )
    (net (code "85") (name "L1") (class "Default")
      (node (ref "B1") (pin "P$3") (pinfunction "K2_P$3") (pintype "bidirectional"))
      (node (ref "B1ALT") (pin "P$3") (pinfunction "K2_P$3") (pintype "bidirectional"))
      (node (ref "R22") (pin "1") (pinfunction "1_1") (pintype "passive"))
    )
    (net (code "86") (name "L2") (class "Default")
      (node (ref "B2") (pin "P$2") (pinfunction "K1_P$2") (pintype "bidirectional"))
      (node (ref "B2ALT") (pin "P$2") (pinfunction "K1_P$2") (pintype "bidirectional"))
      (node (ref "R21") (pin "1") (pinfunction "1_1") (pintype "passive"))
    )
    (net (code "87") (name "L3") (class "Default")
      (node (ref "B2") (pin "P$3") (pinfunction "K2_P$3") (pintype "bidirectional"))
      (node (ref "B2ALT") (pin "P$3") (pinfunction "K2_P$3") (pintype "bidirectional"))
      (node (ref "R20") (pin "1") (pinfunction "1_1") (pintype "passive"))
    )
    (net (code "88") (name "L4") (class "Default")
      (node (ref "B3") (pin "P$2") (pinfunction "K1_P$2") (pintype "bidirectional"))
      (node (ref "B3ALT") (pin "P$2") (pinfunction "K1_P$2") (pintype "bidirectional"))
      (node (ref "R19") (pin "1") (pinfunction "1_1") (pintype "passive"))
    )
    (net (code "89") (name "L5") (class "Default")
      (node (ref "B3") (pin "P$3") (pinfunction "K2_P$3") (pintype "bidirectional"))
      (node (ref "B3ALT") (pin "P$3") (pinfunction "K2_P$3") (pintype "bidirectional"))
      (node (ref "R18") (pin "1") (pinfunction "1_1") (pintype "passive"))
    )
    (net (code "90") (name "L6") (class "Default")
      (node (ref "B4") (pin "P$2") (pinfunction "K1_P$2") (pintype "bidirectional"))
      (node (ref "B4ALT") (pin "P$2") (pinfunction "K1_P$2") (pintype "bidirectional"))
      (node (ref "R17") (pin "1") (pinfunction "1_1") (pintype "passive"))
    )
    (net (code "91") (name "L7") (class "Default")
      (node (ref "B4") (pin "P$3") (pinfunction "K2_P$3") (pintype "bidirectional"))
      (node (ref "B4ALT") (pin "P$3") (pinfunction "K2_P$3") (pintype "bidirectional"))
      (node (ref "R16") (pin "1") (pinfunction "1_1") (pintype "passive"))
    )
    (net (code "92") (name "L8") (class "Default")
      (node (ref "B5") (pin "P$2") (pinfunction "K1_P$2") (pintype "bidirectional"))
      (node (ref "B5ALT") (pin "P$2") (pinfunction "K1_P$2") (pintype "bidirectional"))
      (node (ref "R15") (pin "1") (pinfunction "1_1") (pintype "passive"))
    )
    (net (code "93") (name "L9") (class "Default")
      (node (ref "B5") (pin "P$3") (pinfunction "K2_P$3") (pintype "bidirectional"))
      (node (ref "B5ALT") (pin "P$3") (pinfunction "K2_P$3") (pintype "bidirectional"))
      (node (ref "R14") (pin "1") (pinfunction "1_1") (pintype "passive"))
    )
    (net (code "94") (name "L10") (class "Default")
      (node (ref "B6") (pin "P$2") (pinfunction "K1_P$2") (pintype "bidirectional"))
      (node (ref "B6ALT") (pin "P$2") (pinfunction "K1_P$2") (pintype "bidirectional"))
      (node (ref "R13") (pin "1") (pinfunction "1_1") (pintype "passive"))
    )
    (net (code "95") (name "L11") (class "Default")
      (node (ref "B6") (pin "P$3") (pinfunction "K2_P$3") (pintype "bidirectional"))
      (node (ref "B6ALT") (pin "P$3") (pinfunction "K2_P$3") (pintype "bidirectional"))
      (node (ref "R12") (pin "1") (pinfunction "1_1") (pintype "passive"))
    )
    (net (code "96") (name "L12") (class "Default")
      (node (ref "B7") (pin "P$2") (pinfunction "K1_P$2") (pintype "bidirectional"))
      (node (ref "B7ALT") (pin "P$2") (pinfunction "K1_P$2") (pintype "bidirectional"))
      (node (ref "R11") (pin "1") (pinfunction "1_1") (pintype "passive"))
    )
    (net (code "97") (name "L13") (class "Default")
      (node (ref "B7") (pin "P$3") (pinfunction "K2_P$3") (pintype "bidirectional"))
      (node (ref "B7ALT") (pin "P$3") (pinfunction "K2_P$3") (pintype "bidirectional"))
      (node (ref "R10") (pin "1") (pinfunction "1_1") (pintype "passive"))
    )
    (net (code "98") (name "L14") (class "Default")
      (node (ref "B8") (pin "P$2") (pinfunction "K1_P$2") (pintype "bidirectional"))
      (node (ref "B8ALT") (pin "P$2") (pinfunction "K1_P$2") (pintype "bidirectional"))
      (node (ref "R4") (pin "1") (pinfunction "1_1") (pintype "passive"))
    )
    (net (code "99") (name "L15") (class "Default")
      (node (ref "B8") (pin "P$3") (pinfunction "K2_P$3") (pintype "bidirectional"))
      (node (ref "B8ALT") (pin "P$3") (pinfunction "K2_P$3") (pintype "bidirectional"))
      (node (ref "R3") (pin "1") (pinfunction "1_1") (pintype "passive"))
    )
    (net (code "100") (name "L16") (class "Default")
      (node (ref "B9") (pin "P$2") (pinfunction "K1_P$2") (pintype "bidirectional"))
      (node (ref "B9ALT") (pin "P$2") (pinfunction "K1_P$2") (pintype "bidirectional"))
      (node (ref "R39") (pin "1") (pinfunction "1_1") (pintype "passive"))
    )
    (net (code "101") (name "L17") (class "Default")
      (node (ref "B9") (pin "P$3") (pinfunction "K2_P$3") (pintype "bidirectional"))
      (node (ref "B9ALT") (pin "P$3") (pinfunction "K2_P$3") (pintype "bidirectional"))
      (node (ref "R38") (pin "1") (pinfunction "1_1") (pintype "passive"))
    )
    (net (code "102") (name "L18") (class "Default")
      (node (ref "B10") (pin "P$2") (pinfunction "K1_P$2") (pintype "bidirectional"))
      (node (ref "B10ALT") (pin "P$2") (pinfunction "K1_P$2") (pintype "bidirectional"))
      (node (ref "R37") (pin "1") (pinfunction "1_1") (pintype "passive"))
    )
    (net (code "103") (name "L19") (class "Default")
      (node (ref "B10") (pin "P$3") (pinfunction "K2_P$3") (pintype "bidirectional"))
      (node (ref "B10ALT") (pin "P$3") (pinfunction "K2_P$3") (pintype "bidirectional"))
      (node (ref "R36") (pin "1") (pinfunction "1_1") (pintype "passive"))
    )
    (net (code "104") (name "L20") (class "Default")
      (node (ref "B11") (pin "P$2") (pinfunction "K1_P$2") (pintype "bidirectional"))
      (node (ref "B11ALT") (pin "P$2") (pinfunction "K1_P$2") (pintype "bidirectional"))
      (node (ref "R35") (pin "1") (pinfunction "1_1") (pintype "passive"))
    )
    (net (code "105") (name "L21") (class "Default")
      (node (ref "B11") (pin "P$3") (pinfunction "K2_P$3") (pintype "bidirectional"))
      (node (ref "B11ALT") (pin "P$3") (pinfunction "K2_P$3") (pintype "bidirectional"))
      (node (ref "R34") (pin "1") (pinfunction "1_1") (pintype "passive"))
    )
    (net (code "106") (name "L22") (class "Default")
      (node (ref "B12") (pin "P$2") (pinfunction "K1_P$2") (pintype "bidirectional"))
      (node (ref "B12ALT") (pin "P$2") (pinfunction "K1_P$2") (pintype "bidirectional"))
      (node (ref "R33") (pin "1") (pinfunction "1_1") (pintype "passive"))
    )
    (net (code "107") (name "L23") (class "Default")
      (node (ref "B12") (pin "P$3") (pinfunction "K2_P$3") (pintype "bidirectional"))
      (node (ref "B12ALT") (pin "P$3") (pinfunction "K2_P$3") (pintype "bidirectional"))
      (node (ref "R32") (pin "1") (pinfunction "1_1") (pintype "passive"))
    )
    (net (code "108") (name "L24") (class "Default")
      (node (ref "B13") (pin "P$2") (pinfunction "K1_P$2") (pintype "bidirectional"))
      (node (ref "R31") (pin "1") (pinfunction "1_1") (pintype "passive"))
    )
    (net (code "109") (name "L25") (class "Default")
      (node (ref "B13") (pin "P$3") (pinfunction "K2_P$3") (pintype "bidirectional"))
      (node (ref "R30") (pin "1") (pinfunction "1_1") (pintype "passive"))
    )
    (net (code "110") (name "L26") (class "Default")
      (node (ref "B14") (pin "P$2") (pinfunction "K1_P$2") (pintype "bidirectional"))
      (node (ref "B14ALT") (pin "P$2") (pinfunction "K1_P$2") (pintype "bidirectional"))
      (node (ref "R29") (pin "1") (pinfunction "1_1") (pintype "passive"))
    )
    (net (code "111") (name "L27") (class "Default")
      (node (ref "B14") (pin "P$3") (pinfunction "K2_P$3") (pintype "bidirectional"))
      (node (ref "B14ALT") (pin "P$3") (pinfunction "K2_P$3") (pintype "bidirectional"))
      (node (ref "R28") (pin "1") (pinfunction "1_1") (pintype "passive"))
    )
    (net (code "112") (name "L28") (class "Default")
      (node (ref "B15") (pin "P$2") (pinfunction "K1_P$2") (pintype "bidirectional"))
      (node (ref "R27") (pin "1") (pinfunction "1_1") (pintype "passive"))
    )
    (net (code "113") (name "L29") (class "Default")
      (node (ref "B15") (pin "P$3") (pinfunction "K2_P$3") (pintype "bidirectional"))
      (node (ref "R26") (pin "1") (pinfunction "1_1") (pintype "passive"))
    )
    (net (code "114") (name "L30") (class "Default")
      (node (ref "B16") (pin "P$2") (pinfunction "K1_P$2") (pintype "bidirectional"))
      (node (ref "R25") (pin "1") (pinfunction "1_1") (pintype "passive"))
    )
    (net (code "115") (name "L31") (class "Default")
      (node (ref "B16") (pin "P$3") (pinfunction "K2_P$3") (pintype "bidirectional"))
      (node (ref "R24") (pin "1") (pinfunction "1_1") (pintype "passive"))
    )
    (net (code "116") (name "L32") (class "Default")
      (node (ref "B17") (pin "P$2") (pinfunction "K1_P$2") (pintype "bidirectional"))
      (node (ref "B17ALT") (pin "P$2") (pinfunction "K1_P$2") (pintype "bidirectional"))
      (node (ref "R55") (pin "1") (pinfunction "1_1") (pintype "passive"))
    )
    (net (code "117") (name "L33") (class "Default")
      (node (ref "B17") (pin "P$3") (pinfunction "K2_P$3") (pintype "bidirectional"))
      (node (ref "B17ALT") (pin "P$3") (pinfunction "K2_P$3") (pintype "bidirectional"))
      (node (ref "R54") (pin "1") (pinfunction "1_1") (pintype "passive"))
    )
    (net (code "118") (name "L34") (class "Default")
      (node (ref "B18") (pin "P$2") (pinfunction "K1_P$2") (pintype "bidirectional"))
      (node (ref "R53") (pin "1") (pinfunction "1_1") (pintype "passive"))
    )
    (net (code "119") (name "L35") (class "Default")
      (node (ref "B18") (pin "P$3") (pinfunction "K2_P$3") (pintype "bidirectional"))
      (node (ref "R52") (pin "1") (pinfunction "1_1") (pintype "passive"))
    )
    (net (code "120") (name "L36") (class "Default")
      (node (ref "B19") (pin "P$2") (pinfunction "K1_P$2") (pintype "bidirectional"))
      (node (ref "R51") (pin "1") (pinfunction "1_1") (pintype "passive"))
    )
    (net (code "121") (name "L37") (class "Default")
      (node (ref "B19") (pin "P$3") (pinfunction "K2_P$3") (pintype "bidirectional"))
      (node (ref "R50") (pin "1") (pinfunction "1_1") (pintype "passive"))
    )
    (net (code "122") (name "L38") (class "Default")
      (node (ref "B20") (pin "P$2") (pinfunction "K1_P$2") (pintype "bidirectional"))
      (node (ref "B20ALT") (pin "P$2") (pinfunction "K1_P$2") (pintype "bidirectional"))
      (node (ref "R49") (pin "1") (pinfunction "1_1") (pintype "passive"))
    )
    (net (code "123") (name "L39") (class "Default")
      (node (ref "B20") (pin "P$3") (pinfunction "K2_P$3") (pintype "bidirectional"))
      (node (ref "B20ALT") (pin "P$3") (pinfunction "K2_P$3") (pintype "bidirectional"))
      (node (ref "R48") (pin "1") (pinfunction "1_1") (pintype "passive"))
    )
    (net (code "124") (name "L40") (class "Default")
      (node (ref "B21") (pin "P$2") (pinfunction "K1_P$2") (pintype "bidirectional"))
      (node (ref "B21ALT") (pin "P$2") (pinfunction "K1_P$2") (pintype "bidirectional"))
      (node (ref "R47") (pin "1") (pinfunction "1_1") (pintype "passive"))
    )
    (net (code "125") (name "L41") (class "Default")
      (node (ref "B21") (pin "P$3") (pinfunction "K2_P$3") (pintype "bidirectional"))
      (node (ref "B21ALT") (pin "P$3") (pinfunction "K2_P$3") (pintype "bidirectional"))
      (node (ref "R46") (pin "1") (pinfunction "1_1") (pintype "passive"))
    )
    (net (code "126") (name "L42") (class "Default")
      (node (ref "B22") (pin "P$2") (pinfunction "K1_P$2") (pintype "bidirectional"))
      (node (ref "R45") (pin "1") (pinfunction "1_1") (pintype "passive"))
    )
    (net (code "127") (name "L43") (class "Default")
      (node (ref "B22") (pin "P$3") (pinfunction "K2_P$3") (pintype "bidirectional"))
      (node (ref "R44") (pin "1") (pinfunction "1_1") (pintype "passive"))
    )
    (net (code "128") (name "L44") (class "Default")
      (node (ref "B23") (pin "P$2") (pinfunction "K1_P$2") (pintype "bidirectional"))
      (node (ref "R43") (pin "1") (pinfunction "1_1") (pintype "passive"))
    )
    (net (code "129") (name "L45") (class "Default")
      (node (ref "B23") (pin "P$3") (pinfunction "K2_P$3") (pintype "bidirectional"))
      (node (ref "R42") (pin "1") (pinfunction "1_1") (pintype "passive"))
    )
    (net (code "130") (name "L46") (class "Default")
      (node (ref "B24") (pin "P$2") (pinfunction "K1_P$2") (pintype "bidirectional"))
      (node (ref "R41") (pin "1") (pinfunction "1_1") (pintype "passive"))
    )
    (net (code "131") (name "L47") (class "Default")
      (node (ref "B24") (pin "P$3") (pinfunction "K2_P$3") (pintype "bidirectional"))
      (node (ref "R40") (pin "1") (pinfunction "1_1") (pintype "passive"))
    )
    (net (code "132") (name "L48") (class "Default")
      (node (ref "B25") (pin "P$2") (pinfunction "K1_P$2") (pintype "bidirectional"))
      (node (ref "R71") (pin "1") (pinfunction "1_1") (pintype "passive"))
    )
    (net (code "133") (name "L49") (class "Default")
      (node (ref "B25") (pin "P$3") (pinfunction "K2_P$3") (pintype "bidirectional"))
      (node (ref "R70") (pin "1") (pinfunction "1_1") (pintype "passive"))
    )
    (net (code "134") (name "L50") (class "Default")
      (node (ref "B26") (pin "P$2") (pinfunction "K1_P$2") (pintype "bidirectional"))
      (node (ref "B26ALT") (pin "P$2") (pinfunction "K1_P$2") (pintype "bidirectional"))
      (node (ref "R69") (pin "1") (pinfunction "1_1") (pintype "passive"))
    )
    (net (code "135") (name "L51") (class "Default")
      (node (ref "B26") (pin "P$3") (pinfunction "K2_P$3") (pintype "bidirectional"))
      (node (ref "B26ALT") (pin "P$3") (pinfunction "K2_P$3") (pintype "bidirectional"))
      (node (ref "R68") (pin "1") (pinfunction "1_1") (pintype "passive"))
    )
    (net (code "136") (name "L52") (class "Default")
      (node (ref "B27") (pin "P$2") (pinfunction "K1_P$2") (pintype "bidirectional"))
      (node (ref "B27ALT") (pin "P$2") (pinfunction "K1_P$2") (pintype "bidirectional"))
      (node (ref "R67") (pin "1") (pinfunction "1_1") (pintype "passive"))
    )
    (net (code "137") (name "L53") (class "Default")
      (node (ref "B27") (pin "P$3") (pinfunction "K2_P$3") (pintype "bidirectional"))
      (node (ref "B27ALT") (pin "P$3") (pinfunction "K2_P$3") (pintype "bidirectional"))
      (node (ref "R66") (pin "1") (pinfunction "1_1") (pintype "passive"))
    )
    (net (code "138") (name "L54") (class "Default")
      (node (ref "B28") (pin "P$2") (pinfunction "K1_P$2") (pintype "bidirectional"))
      (node (ref "R65") (pin "1") (pinfunction "1_1") (pintype "passive"))
    )
    (net (code "139") (name "L55") (class "Default")
      (node (ref "B28") (pin "P$3") (pinfunction "K2_P$3") (pintype "bidirectional"))
      (node (ref "R64") (pin "1") (pinfunction "1_1") (pintype "passive"))
    )
    (net (code "140") (name "L56") (class "Default")
      (node (ref "B29") (pin "P$2") (pinfunction "K1_P$2") (pintype "bidirectional"))
      (node (ref "R63") (pin "1") (pinfunction "1_1") (pintype "passive"))
    )
    (net (code "141") (name "L57") (class "Default")
      (node (ref "B29") (pin "P$3") (pinfunction "K2_P$3") (pintype "bidirectional"))
      (node (ref "R62") (pin "1") (pinfunction "1_1") (pintype "passive"))
    )
    (net (code "142") (name "L58") (class "Default")
      (node (ref "B30") (pin "P$2") (pinfunction "K1_P$2") (pintype "bidirectional"))
      (node (ref "R61") (pin "1") (pinfunction "1_1") (pintype "passive"))
    )
    (net (code "143") (name "L59") (class "Default")
      (node (ref "B30") (pin "P$3") (pinfunction "K2_P$3") (pintype "bidirectional"))
      (node (ref "R60") (pin "1") (pinfunction "1_1") (pintype "passive"))
    )
    (net (code "144") (name "MOSI") (class "Default")
      (node (ref "C2") (pin "1") (pinfunction "1_1") (pintype "passive"))
      (node (ref "R2") (pin "1") (pinfunction "1_1") (pintype "passive"))
      (node (ref "SERIAL1") (pin "8") (pinfunction "8_8") (pintype "passive"))
      (node (ref "SERIAL2") (pin "8") (pinfunction "8_8") (pintype "passive"))
      (node (ref "SERIAL3") (pin "8") (pinfunction "8_8") (pintype "passive"))
      (node (ref "SSW1") (pin "6") (pinfunction "SDI_6") (pintype "bidirectional"))
      (node (ref "SSW2") (pin "6") (pinfunction "SDI_6") (pintype "bidirectional"))
    )
    (net (code "145") (name "N$18") (class "Default")
      (node (ref "U1") (pin "53") (pinfunction "53_53") (pintype "bidirectional"))
    )
    (net (code "146") (name "N$19") (class "Default")
      (node (ref "U1") (pin "52") (pinfunction "52_52") (pintype "bidirectional"))
    )
    (net (code "147") (name "N$20") (class "Default")
      (node (ref "U1") (pin "51") (pinfunction "51_51") (pintype "bidirectional"))
    )
    (net (code "148") (name "N$21") (class "Default")
      (node (ref "U1") (pin "50") (pinfunction "50_50") (pintype "bidirectional"))
    )
    (net (code "149") (name "N$24") (class "Default")
      (node (ref "U1") (pin "47") (pinfunction "47_47") (pintype "bidirectional"))
    )
    (net (code "150") (name "N$25") (class "Default")
      (node (ref "U1") (pin "46") (pinfunction "46_46") (pintype "bidirectional"))
    )
    (net (code "151") (name "N$26") (class "Default")
      (node (ref "U1") (pin "45") (pinfunction "45_45") (pintype "bidirectional"))
    )
    (net (code "152") (name "N$27") (class "Default")
      (node (ref "U1") (pin "44") (pinfunction "44_44") (pintype "bidirectional"))
    )
    (net (code "153") (name "N$28") (class "Default")
      (node (ref "U1") (pin "43") (pinfunction "43_43") (pintype "bidirectional"))
    )
    (net (code "154") (name "N$29") (class "Default")
      (node (ref "U1") (pin "42") (pinfunction "42_42") (pintype "bidirectional"))
    )
    (net (code "155") (name "Net-(IC2-L0)") (class "Default")
      (node (ref "IC2") (pin "6") (pinfunction "L0_6") (pintype "output"))
      (node (ref "R23") (pin "2") (pinfunction "2_2") (pintype "passive"))
    )
    (net (code "156") (name "Net-(IC2-L1)") (class "Default")
      (node (ref "IC2") (pin "7") (pinfunction "L1_7") (pintype "output"))
      (node (ref "R22") (pin "2") (pinfunction "2_2") (pintype "passive"))
    )
    (net (code "157") (name "Net-(IC2-L2)") (class "Default")
      (node (ref "IC2") (pin "8") (pinfunction "L2_8") (pintype "output"))
      (node (ref "R21") (pin "2") (pinfunction "2_2") (pintype "passive"))
    )
    (net (code "158") (name "Net-(IC2-L3)") (class "Default")
      (node (ref "IC2") (pin "9") (pinfunction "L3_9") (pintype "output"))
      (node (ref "R20") (pin "2") (pinfunction "2_2") (pintype "passive"))
    )
    (net (code "159") (name "Net-(IC2-L4)") (class "Default")
      (node (ref "IC2") (pin "10") (pinfunction "L4_10") (pintype "output"))
      (node (ref "R19") (pin "2") (pinfunction "2_2") (pintype "passive"))
    )
    (net (code "160") (name "Net-(IC2-L5)") (class "Default")
      (node (ref "IC2") (pin "11") (pinfunction "L5_11") (pintype "output"))
      (node (ref "R18") (pin "2") (pinfunction "2_2") (pintype "passive"))
    )
    (net (code "161") (name "Net-(IC2-L6)") (class "Default")
      (node (ref "IC2") (pin "12") (pinfunction "L6_12") (pintype "output"))
      (node (ref "R17") (pin "2") (pinfunction "2_2") (pintype "passive"))
    )
    (net (code "162") (name "Net-(IC2-L7)") (class "Default")
      (node (ref "IC2") (pin "13") (pinfunction "L7_13") (pintype "output"))
      (node (ref "R16") (pin "2") (pinfunction "2_2") (pintype "passive"))
    )
    (net (code "163") (name "Net-(IC2-L8)") (class "Default")
      (node (ref "IC2") (pin "15") (pinfunction "L8_15") (pintype "output"))
      (node (ref "R15") (pin "2") (pinfunction "2_2") (pintype "passive"))
    )
    (net (code "164") (name "Net-(IC2-L9)") (class "Default")
      (node (ref "IC2") (pin "16") (pinfunction "L9_16") (pintype "output"))
      (node (ref "R14") (pin "2") (pinfunction "2_2") (pintype "passive"))
    )
    (net (code "165") (name "Net-(IC2-L10)") (class "Default")
      (node (ref "IC2") (pin "17") (pinfunction "L10_17") (pintype "output"))
      (node (ref "R13") (pin "2") (pinfunction "2_2") (pintype "passive"))
    )
    (net (code "166") (name "Net-(IC2-L11)") (class "Default")
      (node (ref "IC2") (pin "18") (pinfunction "L11_18") (pintype "output"))
      (node (ref "R12") (pin "2") (pinfunction "2_2") (pintype "passive"))
    )
    (net (code "167") (name "Net-(IC2-L12)") (class "Default")
      (node (ref "IC2") (pin "19") (pinfunction "L12_19") (pintype "output"))
      (node (ref "R11") (pin "2") (pinfunction "2_2") (pintype "passive"))
    )
    (net (code "168") (name "Net-(IC2-L13)") (class "Default")
      (node (ref "IC2") (pin "20") (pinfunction "L13_20") (pintype "output"))
      (node (ref "R10") (pin "2") (pinfunction "2_2") (pintype "passive"))
    )
    (net (code "169") (name "Net-(IC2-L14)") (class "Default")
      (node (ref "IC2") (pin "21") (pinfunction "L14_21") (pintype "output"))
      (node (ref "R4") (pin "2") (pinfunction "2_2") (pintype "passive"))
    )
    (net (code "170") (name "Net-(IC2-L15)") (class "Default")
      (node (ref "IC2") (pin "22") (pinfunction "L15_22") (pintype "output"))
      (node (ref "R3") (pin "2") (pinfunction "2_2") (pintype "passive"))
    )
    (net (code "171") (name "Net-(IC3-L0)") (class "Default")
      (node (ref "IC3") (pin "6") (pinfunction "L0_6") (pintype "output"))
      (node (ref "R39") (pin "2") (pinfunction "2_2") (pintype "passive"))
    )
    (net (code "172") (name "Net-(IC3-L1)") (class "Default")
      (node (ref "IC3") (pin "7") (pinfunction "L1_7") (pintype "output"))
      (node (ref "R38") (pin "2") (pinfunction "2_2") (pintype "passive"))
    )
    (net (code "173") (name "Net-(IC3-L2)") (class "Default")
      (node (ref "IC3") (pin "8") (pinfunction "L2_8") (pintype "output"))
      (node (ref "R37") (pin "2") (pinfunction "2_2") (pintype "passive"))
    )
    (net (code "174") (name "Net-(IC3-L3)") (class "Default")
      (node (ref "IC3") (pin "9") (pinfunction "L3_9") (pintype "output"))
      (node (ref "R36") (pin "2") (pinfunction "2_2") (pintype "passive"))
    )
    (net (code "175") (name "Net-(IC3-L4)") (class "Default")
      (node (ref "IC3") (pin "10") (pinfunction "L4_10") (pintype "output"))
      (node (ref "R35") (pin "2") (pinfunction "2_2") (pintype "passive"))
    )
    (net (code "176") (name "Net-(IC3-L5)") (class "Default")
      (node (ref "IC3") (pin "11") (pinfunction "L5_11") (pintype "output"))
      (node (ref "R34") (pin "2") (pinfunction "2_2") (pintype "passive"))
    )
    (net (code "177") (name "Net-(IC3-L6)") (class "Default")
      (node (ref "IC3") (pin "12") (pinfunction "L6_12") (pintype "output"))
      (node (ref "R33") (pin "2") (pinfunction "2_2") (pintype "passive"))
    )
    (net (code "178") (name "Net-(IC3-L7)") (class "Default")
      (node (ref "IC3") (pin "13") (pinfunction "L7_13") (pintype "output"))
      (node (ref "R32") (pin "2") (pinfunction "2_2") (pintype "passive"))
    )
    (net (code "179") (name "Net-(IC3-L8)") (class "Default")
      (node (ref "IC3") (pin "15") (pinfunction "L8_15") (pintype "output"))
      (node (ref "R31") (pin "2") (pinfunction "2_2") (pintype "passive"))
    )
    (net (code "180") (name "Net-(IC3-L9)") (class "Default")
      (node (ref "IC3") (pin "16") (pinfunction "L9_16") (pintype "output"))
      (node (ref "R30") (pin "2") (pinfunction "2_2") (pintype "passive"))
    )
    (net (code "181") (name "Net-(IC3-L10)") (class "Default")
      (node (ref "IC3") (pin "17") (pinfunction "L10_17") (pintype "output"))
      (node (ref "R29") (pin "2") (pinfunction "2_2") (pintype "passive"))
    )
    (net (code "182") (name "Net-(IC3-L11)") (class "Default")
      (node (ref "IC3") (pin "18") (pinfunction "L11_18") (pintype "output"))
      (node (ref "R28") (pin "2") (pinfunction "2_2") (pintype "passive"))
    )
    (net (code "183") (name "Net-(IC3-L12)") (class "Default")
      (node (ref "IC3") (pin "19") (pinfunction "L12_19") (pintype "output"))
      (node (ref "R27") (pin "2") (pinfunction "2_2") (pintype "passive"))
    )
    (net (code "184") (name "Net-(IC3-L13)") (class "Default")
      (node (ref "IC3") (pin "20") (pinfunction "L13_20") (pintype "output"))
      (node (ref "R26") (pin "2") (pinfunction "2_2") (pintype "passive"))
    )
    (net (code "185") (name "Net-(IC3-L14)") (class "Default")
      (node (ref "IC3") (pin "21") (pinfunction "L14_21") (pintype "output"))
      (node (ref "R25") (pin "2") (pinfunction "2_2") (pintype "passive"))
    )
    (net (code "186") (name "Net-(IC3-L15)") (class "Default")
      (node (ref "IC3") (pin "22") (pinfunction "L15_22") (pintype "output"))
      (node (ref "R24") (pin "2") (pinfunction "2_2") (pintype "passive"))
    )
    (net (code "187") (name "Net-(IC4-L0)") (class "Default")
      (node (ref "IC4") (pin "6") (pinfunction "L0_6") (pintype "output"))
      (node (ref "R55") (pin "2") (pinfunction "2_2") (pintype "passive"))
    )
    (net (code "188") (name "Net-(IC4-L1)") (class "Default")
      (node (ref "IC4") (pin "7") (pinfunction "L1_7") (pintype "output"))
      (node (ref "R54") (pin "2") (pinfunction "2_2") (pintype "passive"))
    )
    (net (code "189") (name "Net-(IC4-L2)") (class "Default")
      (node (ref "IC4") (pin "8") (pinfunction "L2_8") (pintype "output"))
      (node (ref "R53") (pin "2") (pinfunction "2_2") (pintype "passive"))
    )
    (net (code "190") (name "Net-(IC4-L3)") (class "Default")
      (node (ref "IC4") (pin "9") (pinfunction "L3_9") (pintype "output"))
      (node (ref "R52") (pin "2") (pinfunction "2_2") (pintype "passive"))
    )
    (net (code "191") (name "Net-(IC4-L4)") (class "Default")
      (node (ref "IC4") (pin "10") (pinfunction "L4_10") (pintype "output"))
      (node (ref "R51") (pin "2") (pinfunction "2_2") (pintype "passive"))
    )
    (net (code "192") (name "Net-(IC4-L5)") (class "Default")
      (node (ref "IC4") (pin "11") (pinfunction "L5_11") (pintype "output"))
      (node (ref "R50") (pin "2") (pinfunction "2_2") (pintype "passive"))
    )
    (net (code "193") (name "Net-(IC4-L6)") (class "Default")
      (node (ref "IC4") (pin "12") (pinfunction "L6_12") (pintype "output"))
      (node (ref "R49") (pin "2") (pinfunction "2_2") (pintype "passive"))
    )
    (net (code "194") (name "Net-(IC4-L7)") (class "Default")
      (node (ref "IC4") (pin "13") (pinfunction "L7_13") (pintype "output"))
      (node (ref "R48") (pin "2") (pinfunction "2_2") (pintype "passive"))
    )
    (net (code "195") (name "Net-(IC4-L8)") (class "Default")
      (node (ref "IC4") (pin "15") (pinfunction "L8_15") (pintype "output"))
      (node (ref "R47") (pin "2") (pinfunction "2_2") (pintype "passive"))
    )
    (net (code "196") (name "Net-(IC4-L9)") (class "Default")
      (node (ref "IC4") (pin "16") (pinfunction "L9_16") (pintype "output"))
      (node (ref "R46") (pin "2") (pinfunction "2_2") (pintype "passive"))
    )
    (net (code "197") (name "Net-(IC4-L10)") (class "Default")
      (node (ref "IC4") (pin "17") (pinfunction "L10_17") (pintype "output"))
      (node (ref "R45") (pin "2") (pinfunction "2_2") (pintype "passive"))
    )
    (net (code "198") (name "Net-(IC4-L11)") (class "Default")
      (node (ref "IC4") (pin "18") (pinfunction "L11_18") (pintype "output"))
      (node (ref "R44") (pin "2") (pinfunction "2_2") (pintype "passive"))
    )
    (net (code "199") (name "Net-(IC4-L12)") (class "Default")
      (node (ref "IC4") (pin "19") (pinfunction "L12_19") (pintype "output"))
      (node (ref "R43") (pin "2") (pinfunction "2_2") (pintype "passive"))
    )
    (net (code "200") (name "Net-(IC4-L13)") (class "Default")
      (node (ref "IC4") (pin "20") (pinfunction "L13_20") (pintype "output"))
      (node (ref "R42") (pin "2") (pinfunction "2_2") (pintype "passive"))
    )
    (net (code "201") (name "Net-(IC4-L14)") (class "Default")
      (node (ref "IC4") (pin "21") (pinfunction "L14_21") (pintype "output"))
      (node (ref "R41") (pin "2") (pinfunction "2_2") (pintype "passive"))
    )
    (net (code "202") (name "Net-(IC4-L15)") (class "Default")
      (node (ref "IC4") (pin "22") (pinfunction "L15_22") (pintype "output"))
      (node (ref "R40") (pin "2") (pinfunction "2_2") (pintype "passive"))
    )
    (net (code "203") (name "Net-(IC5-L0)") (class "Default")
      (node (ref "IC5") (pin "6") (pinfunction "L0_6") (pintype "output"))
      (node (ref "R71") (pin "2") (pinfunction "2_2") (pintype "passive"))
    )
    (net (code "204") (name "Net-(IC5-L1)") (class "Default")
      (node (ref "IC5") (pin "7") (pinfunction "L1_7") (pintype "output"))
      (node (ref "R70") (pin "2") (pinfunction "2_2") (pintype "passive"))
    )
    (net (code "205") (name "Net-(IC5-L2)") (class "Default")
      (node (ref "IC5") (pin "8") (pinfunction "L2_8") (pintype "output"))
      (node (ref "R69") (pin "2") (pinfunction "2_2") (pintype "passive"))
    )
    (net (code "206") (name "Net-(IC5-L3)") (class "Default")
      (node (ref "IC5") (pin "9") (pinfunction "L3_9") (pintype "output"))
      (node (ref "R68") (pin "2") (pinfunction "2_2") (pintype "passive"))
    )
    (net (code "207") (name "Net-(IC5-L4)") (class "Default")
      (node (ref "IC5") (pin "10") (pinfunction "L4_10") (pintype "output"))
      (node (ref "R67") (pin "2") (pinfunction "2_2") (pintype "passive"))
    )
    (net (code "208") (name "Net-(IC5-L5)") (class "Default")
      (node (ref "IC5") (pin "11") (pinfunction "L5_11") (pintype "output"))
      (node (ref "R66") (pin "2") (pinfunction "2_2") (pintype "passive"))
    )
    (net (code "209") (name "Net-(IC5-L6)") (class "Default")
      (node (ref "IC5") (pin "12") (pinfunction "L6_12") (pintype "output"))
      (node (ref "R65") (pin "2") (pinfunction "2_2") (pintype "passive"))
    )
    (net (code "210") (name "Net-(IC5-L7)") (class "Default")
      (node (ref "IC5") (pin "13") (pinfunction "L7_13") (pintype "output"))
      (node (ref "R64") (pin "2") (pinfunction "2_2") (pintype "passive"))
    )
    (net (code "211") (name "Net-(IC5-L8)") (class "Default")
      (node (ref "IC5") (pin "15") (pinfunction "L8_15") (pintype "output"))
      (node (ref "R63") (pin "2") (pinfunction "2_2") (pintype "passive"))
    )
    (net (code "212") (name "Net-(IC5-L9)") (class "Default")
      (node (ref "IC5") (pin "16") (pinfunction "L9_16") (pintype "output"))
      (node (ref "R62") (pin "2") (pinfunction "2_2") (pintype "passive"))
    )
    (net (code "213") (name "Net-(IC5-L10)") (class "Default")
      (node (ref "IC5") (pin "17") (pinfunction "L10_17") (pintype "output"))
      (node (ref "R61") (pin "2") (pinfunction "2_2") (pintype "passive"))
    )
    (net (code "214") (name "Net-(IC5-L11)") (class "Default")
      (node (ref "IC5") (pin "18") (pinfunction "L11_18") (pintype "output"))
      (node (ref "R60") (pin "2") (pinfunction "2_2") (pintype "passive"))
    )
    (net (code "215") (name "Net-(IC9A-I)") (class "Default")
      (node (ref "C24") (pin "1") (pinfunction "1_1") (pintype "passive"))
      (node (ref "IC9") (pin "13") (pinfunction "I_13") (pintype "input"))
      (node (ref "R56") (pin "1") (pinfunction "1_1") (pintype "passive"))
    )
    (net (code "216") (name "Net-(JOYSTICKS-Pad7)") (class "Default")
      (node (ref "JOYSTICKS") (pin "7") (pinfunction "7_7") (pintype "passive"))
      (node (ref "L6") (pin "2") (pinfunction "2_2") (pintype "passive"))
    )
    (net (code "217") (name "Net-(L1-Pad2)") (class "Default")
      (node (ref "L1") (pin "2") (pinfunction "2_2") (pintype "passive"))
      (node (ref "SJ1") (pin "2") (pinfunction "2_2") (pintype "passive"))
      (node (ref "SJ2") (pin "1") (pinfunction "1_1") (pintype "passive"))
    )
    (net (code "218") (name "Net-(L2-Pad1)") (class "Default")
      (node (ref "L2") (pin "1") (pinfunction "1_1") (pintype "passive"))
      (node (ref "SERIAL2") (pin "2") (pinfunction "2_2") (pintype "passive"))
    )
    (net (code "219") (name "Net-(R1-Pad2)") (class "Default")
      (node (ref "R1") (pin "2") (pinfunction "2_2") (pintype "passive"))
      (node (ref "U1") (pin "48") (pinfunction "48_48") (pintype "bidirectional"))
    )
    (net (code "220") (name "Net-(R2-Pad2)") (class "Default")
      (node (ref "R2") (pin "2") (pinfunction "2_2") (pintype "passive"))
      (node (ref "U1") (pin "49") (pinfunction "49_49") (pintype "bidirectional"))
    )
    (net (code "221") (name "Net-(R56-Pad2)") (class "Default")
      (node (ref "R56") (pin "2") (pinfunction "2_2") (pintype "passive"))
      (node (ref "R58") (pin "1") (pinfunction "1_1") (pintype "passive"))
      (node (ref "SW1") (pin "B") (pinfunction "B_B") (pintype "passive"))
      (node (ref "U$66") (pin "2") (pinfunction "2_2") (pintype "passive"))
    )
    (net (code "222") (name "Net-(SJ1-Pad1)") (class "Default")
      (node (ref "SJ1") (pin "1") (pinfunction "1_1") (pintype "passive"))
      (node (ref "UART1") (pin "10") (pinfunction "10_10") (pintype "passive"))
    )
    (net (code "223") (name "Net-(SJ2-Pad2)") (class "Default")
      (node (ref "SJ2") (pin "2") (pinfunction "2_2") (pintype "passive"))
      (node (ref "UART1") (pin "9") (pinfunction "9_9") (pintype "passive"))
    )
    (net (code "224") (name "Net-(U$1-P$2)") (class "Default")
      (node (ref "R8") (pin "1") (pinfunction "1_1") (pintype "passive"))
      (node (ref "U$1") (pin "A2") (pinfunction "P$2_A2") (pintype "bidirectional"))
    )
    (net (code "225") (name "Net-(U$1-P$3)") (class "Default")
      (node (ref "R7") (pin "1") (pinfunction "1_1") (pintype "passive"))
      (node (ref "U$1") (pin "A3") (pinfunction "P$3_A3") (pintype "bidirectional"))
    )
    (net (code "226") (name "RESET") (class "Default")
      (node (ref "RESET") (pin "3") (pinfunction "3_3") (pintype "passive"))
      (node (ref "RESETA") (pin "3") (pinfunction "3_3") (pintype "passive"))
      (node (ref "U1") (pin "RESET") (pinfunction "RESET_RESET") (pintype "bidirectional"))
    )
    (net (code "227") (name "RXD1") (class "Default")
      (node (ref "U1") (pin "19") (pinfunction "19(RX1)_19") (pintype "bidirectional"))
      (node (ref "UART1") (pin "2") (pinfunction "2_2") (pintype "passive"))
    )
    (net (code "228") (name "RXD2") (class "Default")
      (node (ref "U1") (pin "17") (pinfunction "17(RX2)_17") (pintype "bidirectional"))
    )
    (net (code "229") (name "RXD3") (class "Default")
      (node (ref "U1") (pin "15") (pinfunction "15(RX3)_15") (pintype "bidirectional"))
    )
    (net (code "230") (name "SCLK") (class "Default")
      (node (ref "C1") (pin "1") (pinfunction "1_1") (pintype "passive"))
      (node (ref "R1") (pin "1") (pinfunction "1_1") (pintype "passive"))
      (node (ref "SERIAL1") (pin "7") (pinfunction "7_7") (pintype "passive"))
      (node (ref "SERIAL2") (pin "7") (pinfunction "7_7") (pintype "passive"))
      (node (ref "SERIAL3") (pin "7") (pinfunction "7_7") (pintype "passive"))
      (node (ref "SSW1") (pin "7") (pinfunction "SCK_7") (pintype "bidirectional"))
      (node (ref "SSW2") (pin "7") (pinfunction "SCK_7") (pintype "bidirectional"))
    )
    (net (code "231") (name "SW1") (class "Default")
      (node (ref "JOYSTICKS") (pin "1") (pinfunction "1_1") (pintype "passive"))
      (node (ref "U1") (pin "35") (pinfunction "35_35") (pintype "bidirectional"))
    )
    (net (code "232") (name "SW2") (class "Default")
      (node (ref "JOYSTICKS") (pin "4") (pinfunction "4_4") (pintype "passive"))
      (node (ref "U1") (pin "36") (pinfunction "36_36") (pintype "bidirectional"))
    )
    (net (code "233") (name "TXD1") (class "Default")
      (node (ref "U1") (pin "18") (pinfunction "18(TX1)_18") (pintype "bidirectional"))
      (node (ref "UART1") (pin "3") (pinfunction "3_3") (pintype "passive"))
    )
    (net (code "234") (name "TXD2") (class "Default")
      (node (ref "U1") (pin "16") (pinfunction "16(TX2)_16") (pintype "bidirectional"))
    )
    (net (code "235") (name "TXD3") (class "Default")
      (node (ref "U1") (pin "14") (pinfunction "14(TX3)_14") (pintype "bidirectional"))
    )
    (net (code "236") (name "VIN") (class "Default")
      (node (ref "U1") (pin "VIN") (pinfunction "VIN_VIN") (pintype "bidirectional"))
    )
    (net (code "237") (name "unconnected-(IC1-INTA-Pad20)") (class "Default")
      (node (ref "IC1") (pin "20") (pinfunction "INTA_20") (pintype "output"))
    )
    (net (code "238") (name "unconnected-(IC1-INTB-Pad19)") (class "Default")
      (node (ref "IC1") (pin "19") (pinfunction "INTB_19") (pintype "output"))
    )
    (net (code "239") (name "unconnected-(IC5-L12-Pad19)") (class "Default")
      (node (ref "IC5") (pin "19") (pinfunction "L12_19") (pintype "output"))
    )
    (net (code "240") (name "unconnected-(IC5-L13-Pad20)") (class "Default")
      (node (ref "IC5") (pin "20") (pinfunction "L13_20") (pintype "output"))
    )
    (net (code "241") (name "unconnected-(IC5-L14-Pad21)") (class "Default")
      (node (ref "IC5") (pin "21") (pinfunction "L14_21") (pintype "output"))
    )
    (net (code "242") (name "unconnected-(IC5-L15-Pad22)") (class "Default")
      (node (ref "IC5") (pin "22") (pinfunction "L15_22") (pintype "output"))
    )
    (net (code "243") (name "unconnected-(IC6-INTA-Pad20)") (class "Default")
      (node (ref "IC6") (pin "20") (pinfunction "INTA_20") (pintype "output"))
    )
    (net (code "244") (name "unconnected-(IC6-INTB-Pad19)") (class "Default")
      (node (ref "IC6") (pin "19") (pinfunction "INTB_19") (pintype "output"))
    )
    (net (code "245") (name "unconnected-(IC7-GPA2-Pad23)") (class "Default")
      (node (ref "IC7") (pin "23") (pinfunction "GPA2_23") (pintype "bidirectional"))
    )
    (net (code "246") (name "unconnected-(IC7-GPA3-Pad24)") (class "Default")
      (node (ref "IC7") (pin "24") (pinfunction "GPA3_24") (pintype "bidirectional"))
    )
    (net (code "247") (name "unconnected-(IC7-GPA4-Pad25)") (class "Default")
      (node (ref "IC7") (pin "25") (pinfunction "GPA4_25") (pintype "bidirectional"))
    )
    (net (code "248") (name "unconnected-(IC7-GPA5-Pad26)") (class "Default")
      (node (ref "IC7") (pin "26") (pinfunction "GPA5_26") (pintype "bidirectional"))
    )
    (net (code "249") (name "unconnected-(IC7-GPA6-Pad27)") (class "Default")
      (node (ref "IC7") (pin "27") (pinfunction "GPA6_27") (pintype "bidirectional"))
    )
    (net (code "250") (name "unconnected-(IC7-GPA7-Pad28)") (class "Default")
      (node (ref "IC7") (pin "28") (pinfunction "GPA7_28") (pintype "bidirectional"))
    )
    (net (code "251") (name "unconnected-(IC7-GPB2-Pad3)") (class "Default")
      (node (ref "IC7") (pin "3") (pinfunction "GPB2_3") (pintype "bidirectional"))
    )
    (net (code "252") (name "unconnected-(IC7-GPB3-Pad4)") (class "Default")
      (node (ref "IC7") (pin "4") (pinfunction "GPB3_4") (pintype "bidirectional"))
    )
    (net (code "253") (name "unconnected-(IC7-GPB4-Pad5)") (class "Default")
      (node (ref "IC7") (pin "5") (pinfunction "GPB4_5") (pintype "bidirectional"))
    )
    (net (code "254") (name "unconnected-(IC7-GPB5-Pad6)") (class "Default")
      (node (ref "IC7") (pin "6") (pinfunction "GPB5_6") (pintype "bidirectional"))
    )
    (net (code "255") (name "unconnected-(IC7-GPB6-Pad7)") (class "Default")
      (node (ref "IC7") (pin "7") (pinfunction "GPB6_7") (pintype "bidirectional"))
    )
    (net (code "256") (name "unconnected-(IC7-GPB7-Pad8)") (class "Default")
      (node (ref "IC7") (pin "8") (pinfunction "GPB7_8") (pintype "bidirectional"))
    )
    (net (code "257") (name "unconnected-(IC7-INTA-Pad20)") (class "Default")
      (node (ref "IC7") (pin "20") (pinfunction "INTA_20") (pintype "output"))
    )
    (net (code "258") (name "unconnected-(IC7-INTB-Pad19)") (class "Default")
      (node (ref "IC7") (pin "19") (pinfunction "INTB_19") (pintype "output"))
    )
    (net (code "259") (name "unconnected-(IC8-GPA2-Pad23)") (class "Default")
      (node (ref "IC8") (pin "23") (pinfunction "GPA2_23") (pintype "bidirectional"))
    )
    (net (code "260") (name "unconnected-(IC8-GPA3-Pad24)") (class "Default")
      (node (ref "IC8") (pin "24") (pinfunction "GPA3_24") (pintype "bidirectional"))
    )
    (net (code "261") (name "unconnected-(IC8-GPA4-Pad25)") (class "Default")
      (node (ref "IC8") (pin "25") (pinfunction "GPA4_25") (pintype "bidirectional"))
    )
    (net (code "262") (name "unconnected-(IC8-GPA5-Pad26)") (class "Default")
      (node (ref "IC8") (pin "26") (pinfunction "GPA5_26") (pintype "bidirectional"))
    )
    (net (code "263") (name "unconnected-(IC8-GPA6-Pad27)") (class "Default")
      (node (ref "IC8") (pin "27") (pinfunction "GPA6_27") (pintype "bidirectional"))
    )
    (net (code "264") (name "unconnected-(IC8-GPA7-Pad28)") (class "Default")
      (node (ref "IC8") (pin "28") (pinfunction "GPA7_28") (pintype "bidirectional"))
    )
    (net (code "265") (name "unconnected-(IC8-GPB1-Pad2)") (class "Default")
      (node (ref "IC8") (pin "2") (pinfunction "GPB1_2") (pintype "bidirectional"))
    )
    (net (code "266") (name "unconnected-(IC8-GPB2-Pad3)") (class "Default")
      (node (ref "IC8") (pin "3") (pinfunction "GPB2_3") (pintype "bidirectional"))
    )
    (net (code "267") (name "unconnected-(IC8-GPB3-Pad4)") (class "Default")
      (node (ref "IC8") (pin "4") (pinfunction "GPB3_4") (pintype "bidirectional"))
    )
    (net (code "268") (name "unconnected-(IC8-GPB4-Pad5)") (class "Default")
      (node (ref "IC8") (pin "5") (pinfunction "GPB4_5") (pintype "bidirectional"))
    )
    (net (code "269") (name "unconnected-(IC8-GPB5-Pad6)") (class "Default")
      (node (ref "IC8") (pin "6") (pinfunction "GPB5_6") (pintype "bidirectional"))
    )
    (net (code "270") (name "unconnected-(IC8-GPB6-Pad7)") (class "Default")
      (node (ref "IC8") (pin "7") (pinfunction "GPB6_7") (pintype "bidirectional"))
    )
    (net (code "271") (name "unconnected-(IC8-GPB7-Pad8)") (class "Default")
      (node (ref "IC8") (pin "8") (pinfunction "GPB7_8") (pintype "bidirectional"))
    )
    (net (code "272") (name "unconnected-(IC8-INTA-Pad20)") (class "Default")
      (node (ref "IC8") (pin "20") (pinfunction "INTA_20") (pintype "output"))
    )
    (net (code "273") (name "unconnected-(IC8-INTB-Pad19)") (class "Default")
      (node (ref "IC8") (pin "19") (pinfunction "INTB_19") (pintype "output"))
    )
    (net (code "274") (name "unconnected-(IC9B-O-Pad10)") (class "Default")
      (node (ref "IC9") (pin "10") (pinfunction "O_10") (pintype "output"))
    )
    (net (code "275") (name "unconnected-(IC9C-O-Pad8)") (class "Default")
      (node (ref "IC9") (pin "8") (pinfunction "O_8") (pintype "output"))
    )
    (net (code "276") (name "unconnected-(IC9D-O-Pad2)") (class "Default")
      (node (ref "IC9") (pin "2") (pinfunction "O_2") (pintype "output"))
    )
    (net (code "277") (name "unconnected-(IC9E-O-Pad4)") (class "Default")
      (node (ref "IC9") (pin "4") (pinfunction "O_4") (pintype "output"))
    )
    (net (code "278") (name "unconnected-(IC9F-O-Pad6)") (class "Default")
      (node (ref "IC9") (pin "6") (pinfunction "O_6") (pintype "output"))
    )
    (net (code "279") (name "unconnected-(JP1-Pad1)") (class "Default")
      (node (ref "JP1") (pin "1") (pinfunction "1_1") (pintype "passive"))
    )
    (net (code "280") (name "unconnected-(JP1-Pad2)") (class "Default")
      (node (ref "JP1") (pin "2") (pinfunction "2_2") (pintype "passive"))
    )
    (net (code "281") (name "unconnected-(JP2-Pad1)") (class "Default")
      (node (ref "JP2") (pin "1") (pinfunction "1_1") (pintype "passive"))
    )
    (net (code "282") (name "unconnected-(JP2-Pad2)") (class "Default")
      (node (ref "JP2") (pin "2") (pinfunction "2_2") (pintype "passive"))
    )
    (net (code "283") (name "unconnected-(SERIAL1-Pad6)") (class "Default")
      (node (ref "SERIAL1") (pin "6") (pinfunction "6_6") (pintype "passive"))
    )
    (net (code "284") (name "unconnected-(SERIAL2-Pad6)") (class "Default")
      (node (ref "SERIAL2") (pin "6") (pinfunction "6_6") (pintype "passive"))
    )
    (net (code "285") (name "unconnected-(SERIAL3-Pad6)") (class "Default")
      (node (ref "SERIAL3") (pin "6") (pinfunction "6_6") (pintype "passive"))
    )
    (net (code "286") (name "unconnected-(SSW1-SDO-Pad5)") (class "Default")
      (node (ref "SSW1") (pin "5") (pinfunction "SDO_5") (pintype "bidirectional"))
    )
    (net (code "287") (name "unconnected-(SSW2-SDO-Pad5)") (class "Default")
      (node (ref "SSW2") (pin "5") (pinfunction "SDO_5") (pintype "bidirectional"))
    )
    (net (code "288") (name "unconnected-(U$34-PadA1)") (class "Default")
      (node (ref "U$34") (pin "A1") (pinfunction "A1_A1") (pintype "passive"))
    )
    (net (code "289") (name "unconnected-(U1-0(RX0)-Pad0)") (class "Default")
      (node (ref "U1") (pin "0") (pinfunction "0(RX0)_0") (pintype "bidirectional"))
    )
    (net (code "290") (name "unconnected-(U1-1(TX0)-Pad1)") (class "Default")
      (node (ref "U1") (pin "1") (pinfunction "1(TX0)_1") (pintype "bidirectional"))
    )
    (net (code "291") (name "unconnected-(U1-Pad2)") (class "Default")
      (node (ref "U1") (pin "2") (pinfunction "2_2") (pintype "bidirectional"))
    )
    (net (code "292") (name "unconnected-(U1-Pad3)") (class "Default")
      (node (ref "U1") (pin "3") (pinfunction "3_3") (pintype "bidirectional"))
    )
    (net (code "293") (name "unconnected-(U1-Pad3.3V)") (class "Default")
      (node (ref "U1") (pin "3.3V") (pinfunction "3.3V_3.3V") (pintype "bidirectional"))
    )
    (net (code "294") (name "unconnected-(U1-Pad4)") (class "Default")
      (node (ref "U1") (pin "4") (pinfunction "4_4") (pintype "bidirectional"))
    )
    (net (code "295") (name "unconnected-(U1-Pad5)") (class "Default")
      (node (ref "U1") (pin "5") (pinfunction "5_5") (pintype "bidirectional"))
    )
    (net (code "296") (name "unconnected-(U1-Pad10)") (class "Default")
      (node (ref "U1") (pin "10") (pinfunction "10_10") (pintype "bidirectional"))
    )
    (net (code "297") (name "unconnected-(U1-Pad11)") (class "Default")
      (node (ref "U1") (pin "11") (pinfunction "11_11") (pintype "bidirectional"))
    )
    (net (code "298") (name "unconnected-(U1-Pad12)") (class "Default")
      (node (ref "U1") (pin "12") (pinfunction "12_12") (pintype "bidirectional"))
    )
    (net (code "299") (name "unconnected-(U1-Pad13)") (class "Default")
      (node (ref "U1") (pin "13") (pinfunction "13_13") (pintype "bidirectional"))
    )
    (net (code "300") (name "unconnected-(U1-PadAREF)") (class "Default")
      (node (ref "U1") (pin "AREF") (pinfunction "AREF_AREF") (pintype "bidirectional"))
    )
    (net (code "301") (name "unconnected-(UART1-Pad1)") (class "Default")
      (node (ref "UART1") (pin "1") (pinfunction "1_1") (pintype "passive"))
    )
    (net (code "302") (name "unconnected-(UART1-Pad4)") (class "Default")
      (node (ref "UART1") (pin "4") (pinfunction "4_4") (pintype "passive"))
    )
    (net (code "303") (name "unconnected-(UART1-Pad6)") (class "Default")
      (node (ref "UART1") (pin "6") (pinfunction "6_6") (pintype "passive"))
    )
    (net (code "304") (name "unconnected-(UART1-Pad7)") (class "Default")
      (node (ref "UART1") (pin "7") (pinfunction "7_7") (pintype "passive"))
    )
    (net (code "305") (name "unconnected-(UART1-Pad8)") (class "Default")
      (node (ref "UART1") (pin "8") (pinfunction "8_8") (pintype "passive"))
    )
  )
)
